# servo-ctrl.net
KiCad netlist of a schematic drawn in EAGLE
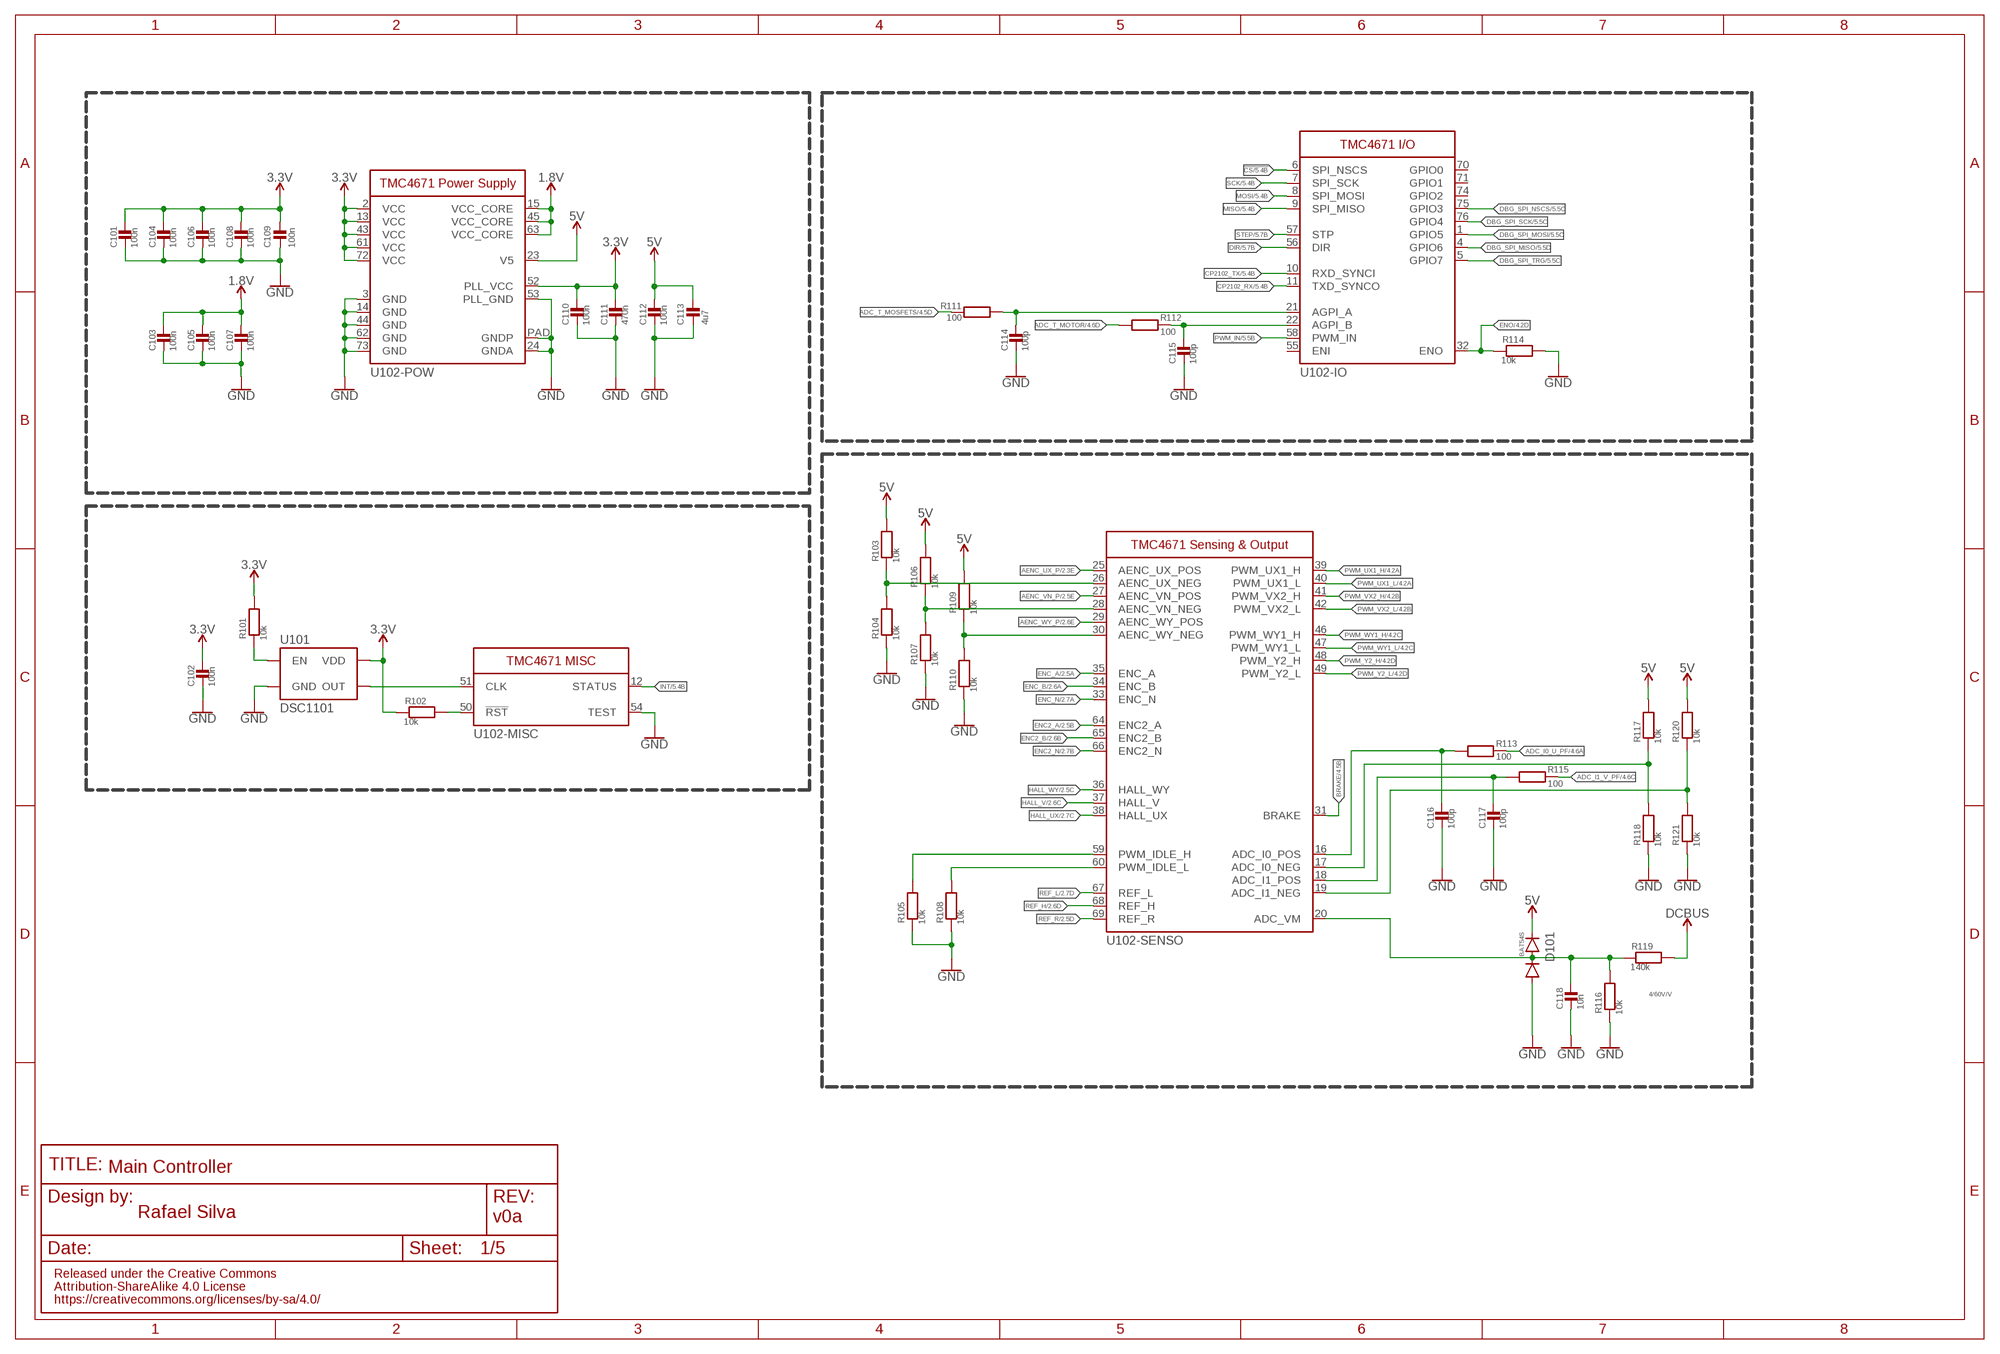
[diagram p0: schematic, sheet 1]
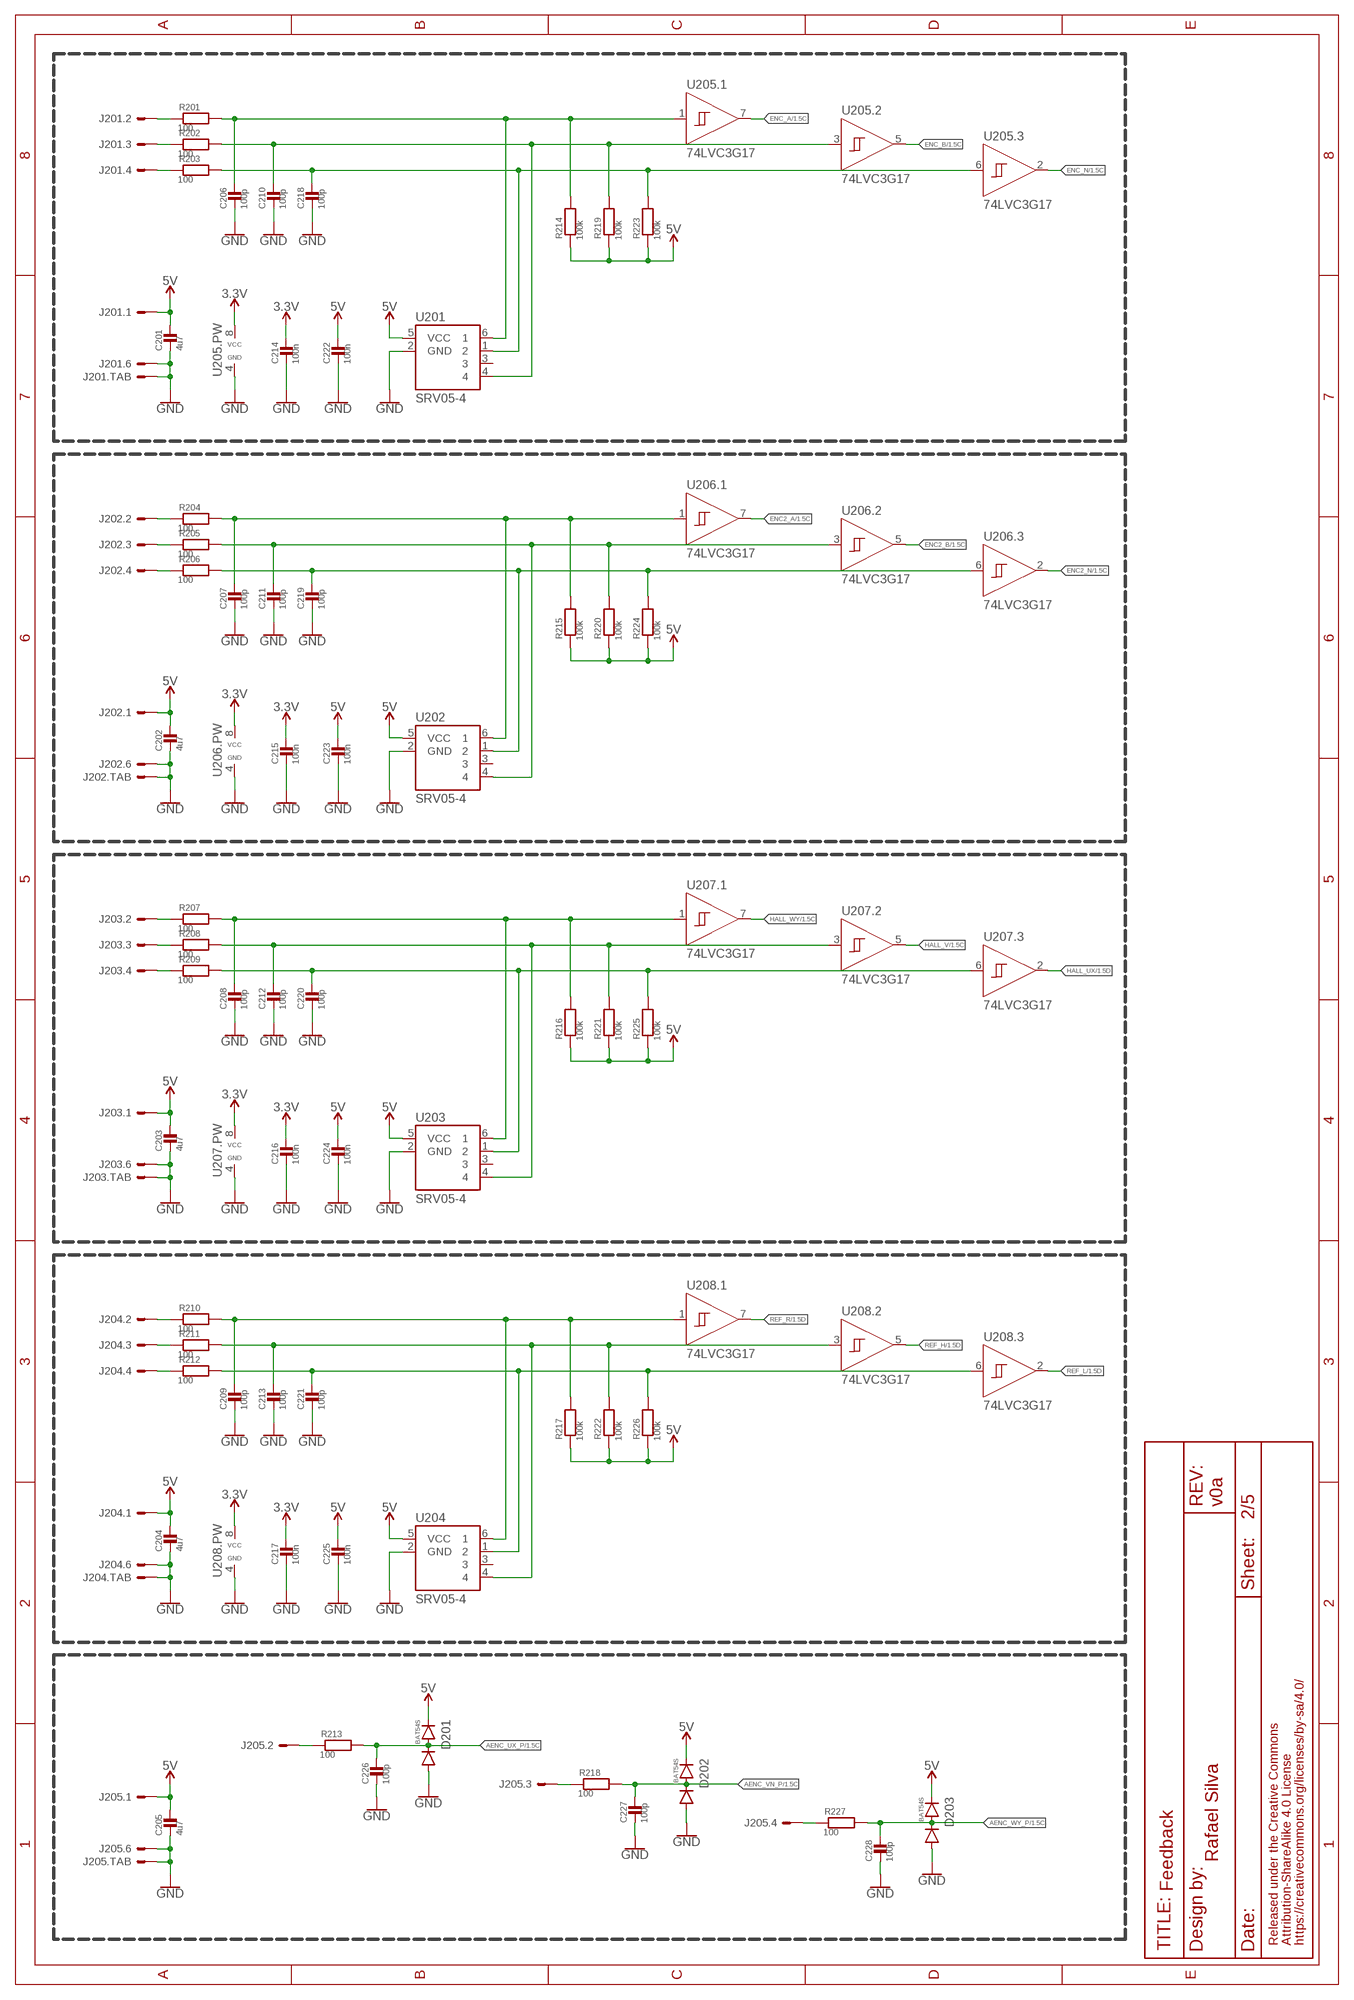
[diagram p1: schematic, sheet 2]
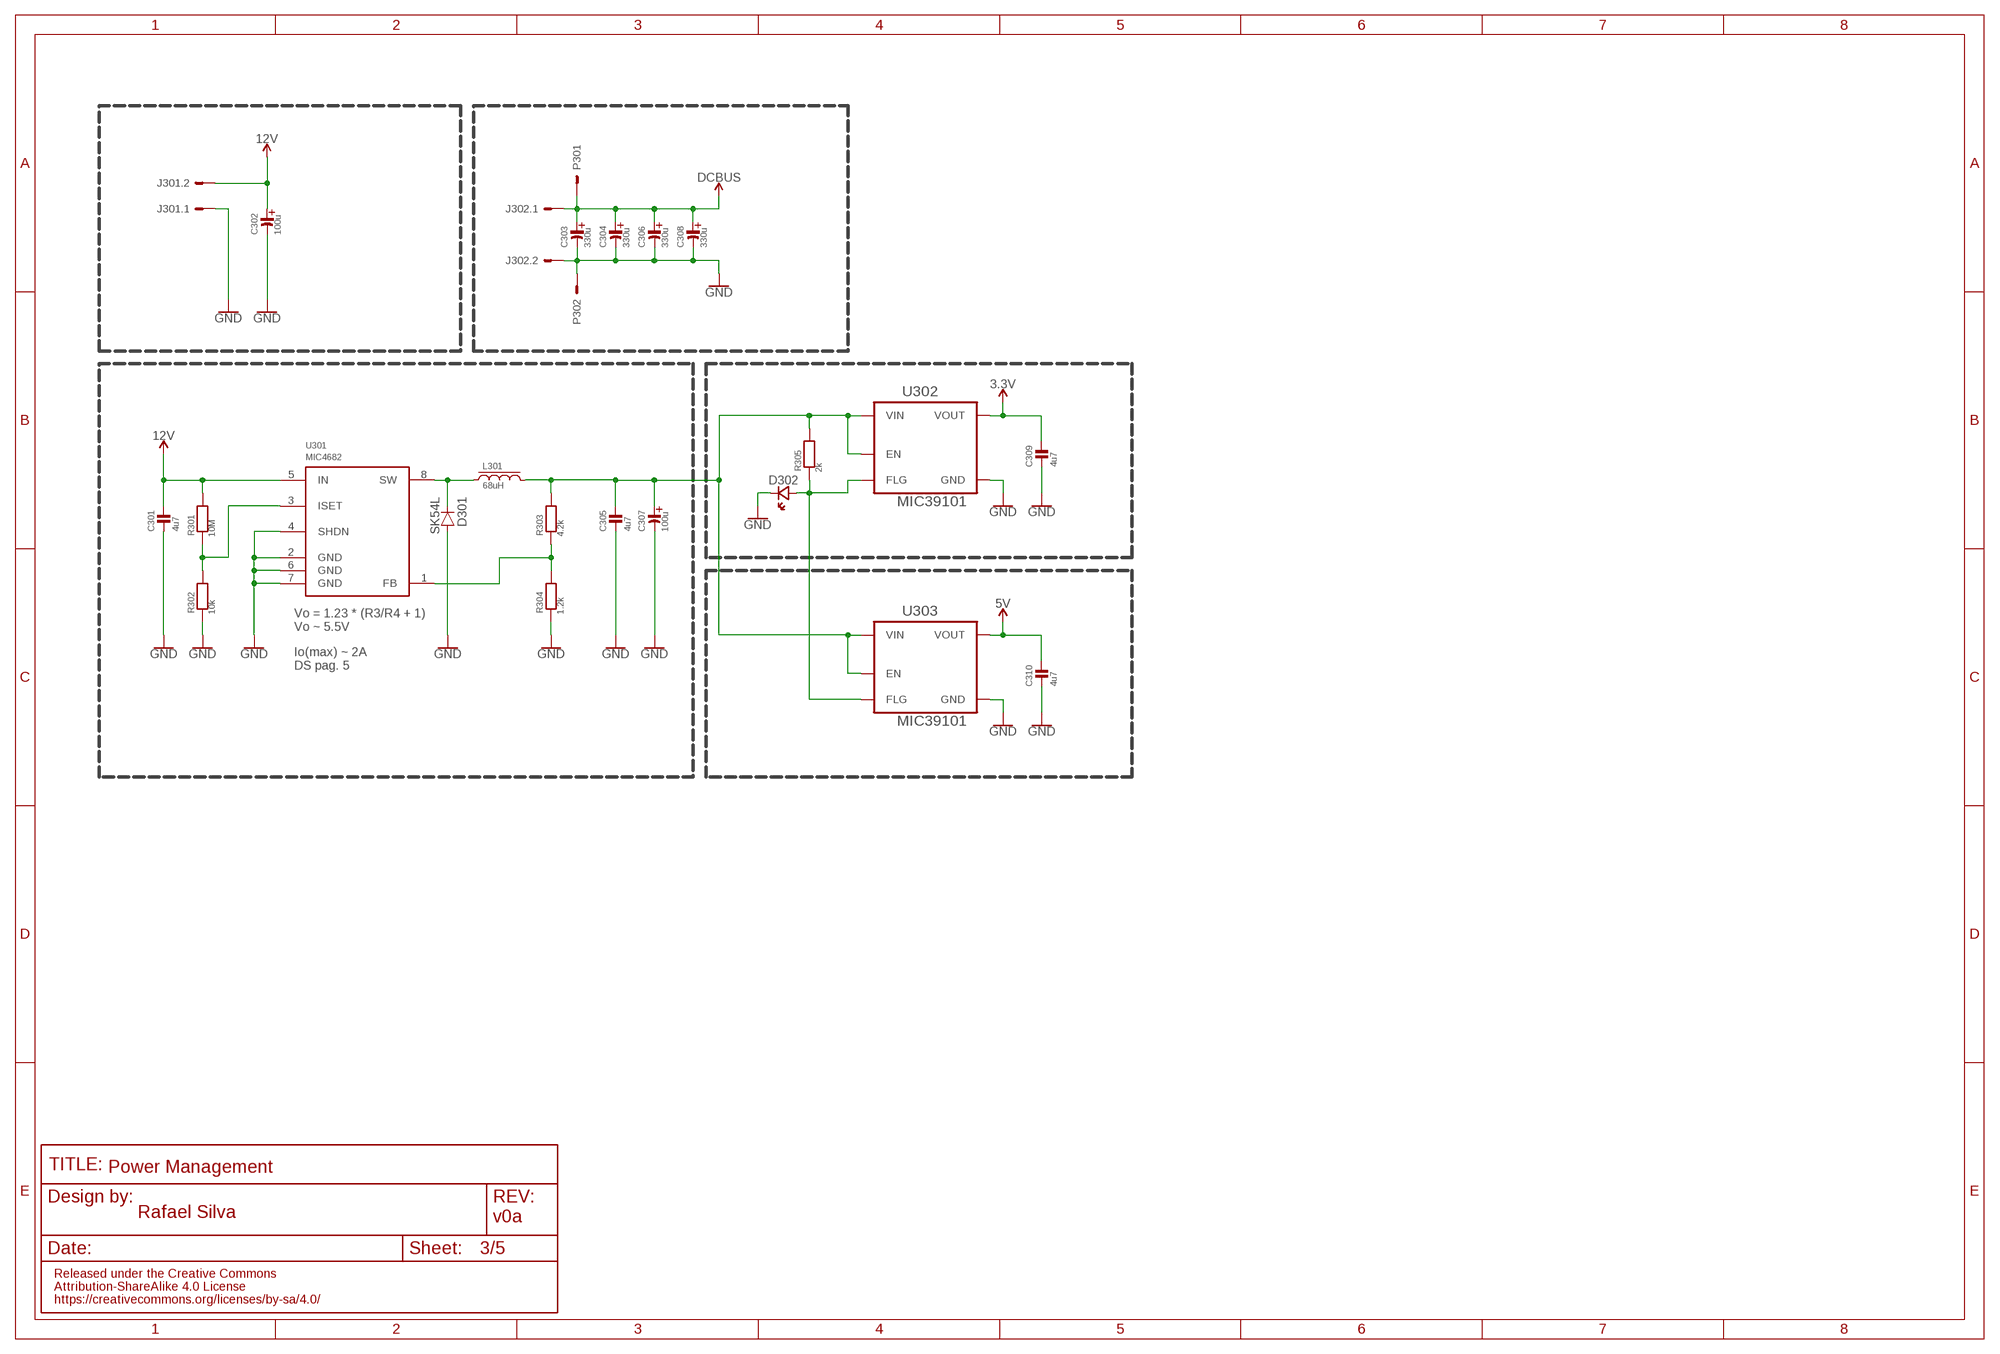
[diagram p2: schematic, sheet 3]
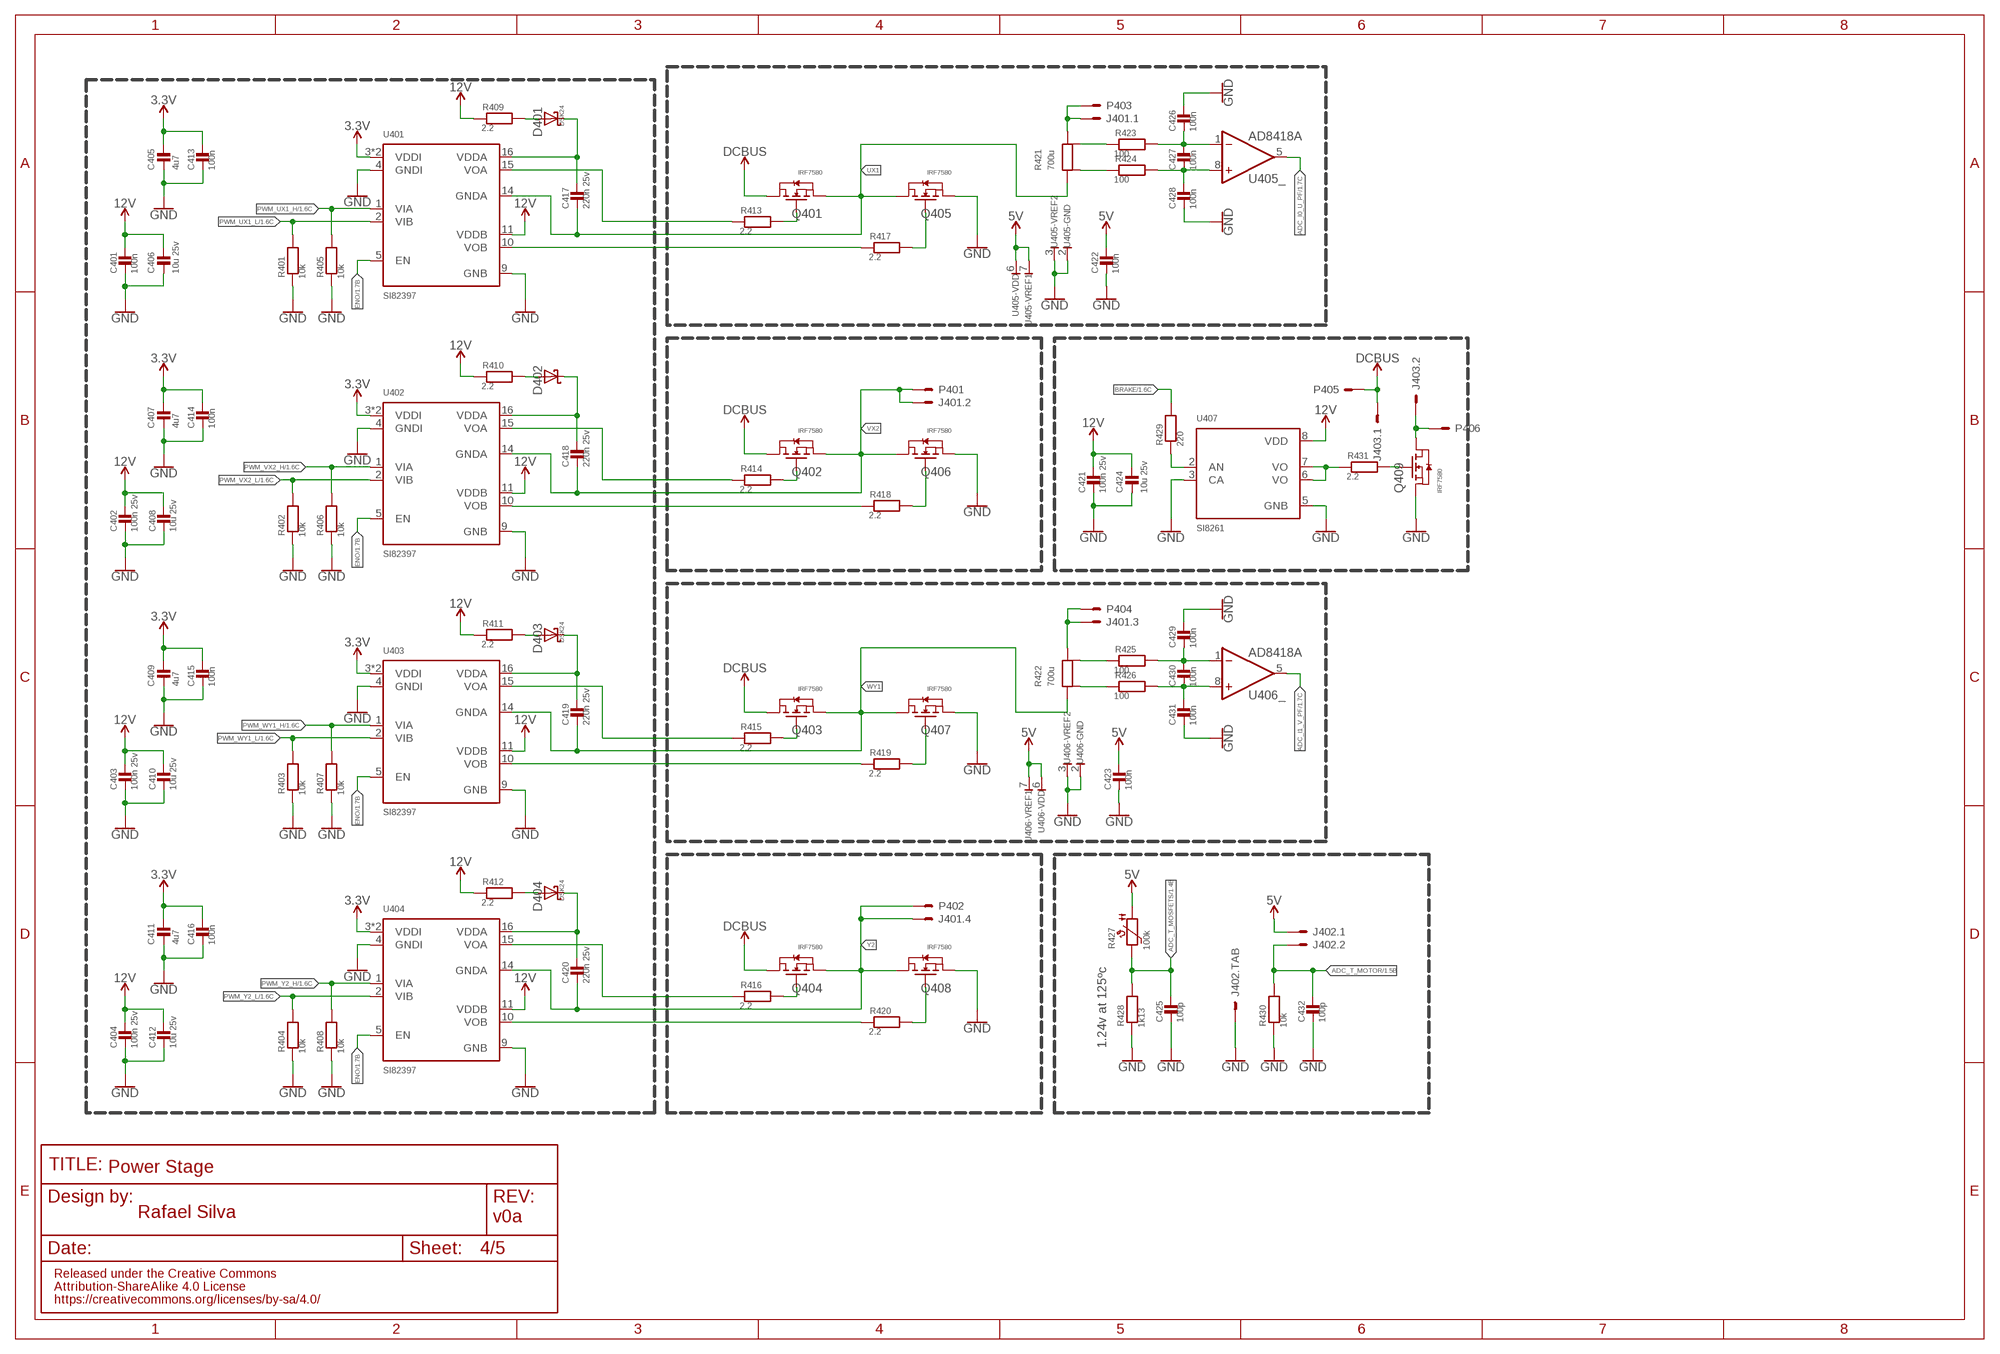
[diagram p3: schematic, sheet 4]
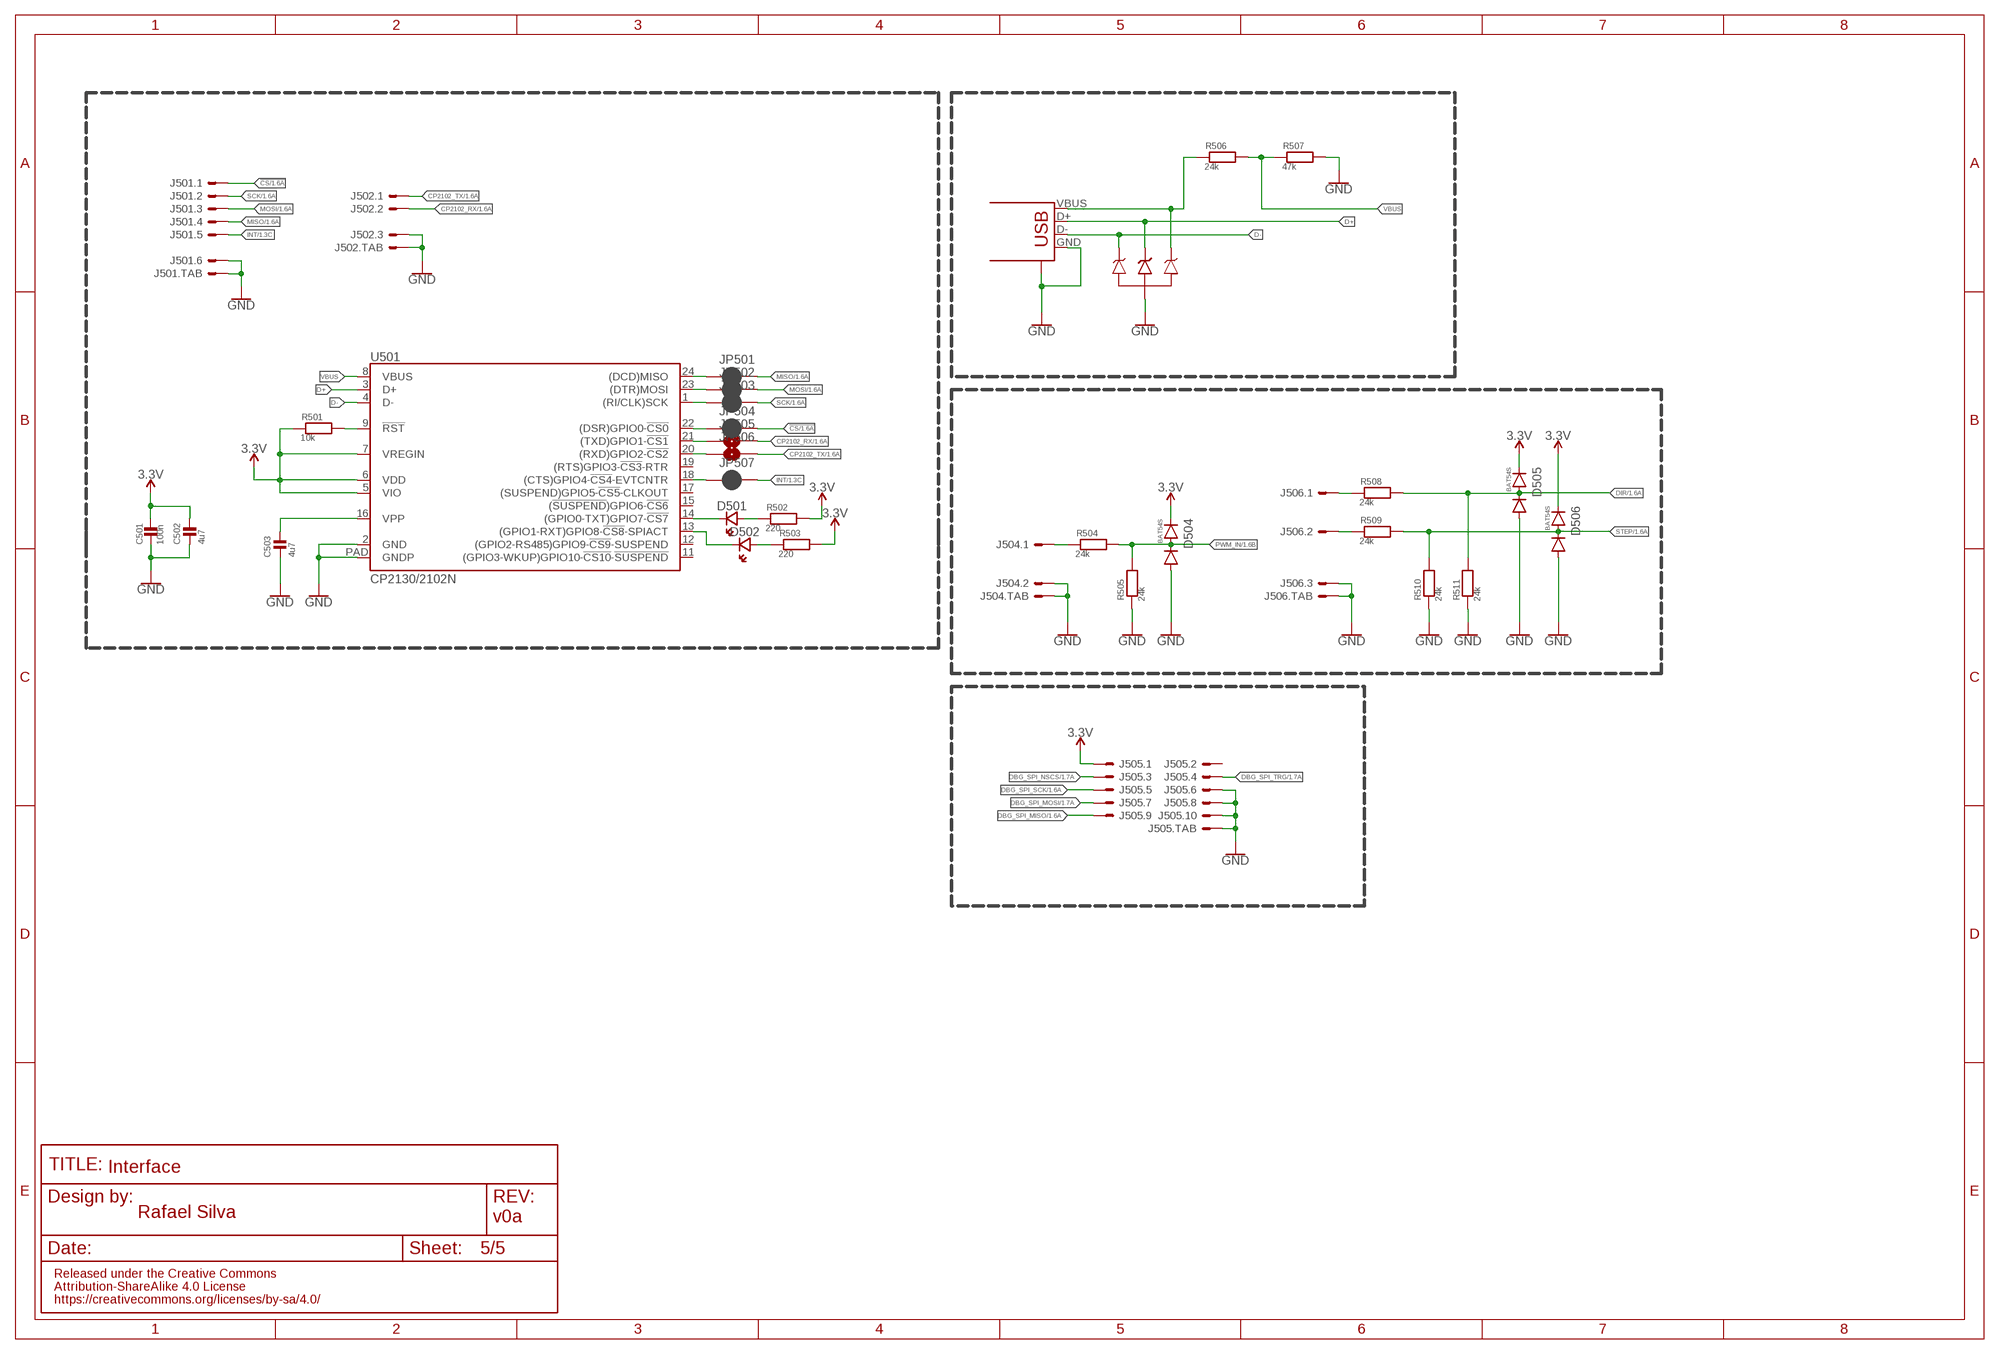
[diagram p4: schematic, sheet 5]

(export (version "E")
  (design (tool "Eeschema 10.0.6"))
  (components
    (comp (ref "C501")
      (value "100n")
      (footprint "eagle-import:0603_WAVE")
      (libsource (lib "eagle-import") (part "MLCC0603"))
    )
    (comp (ref "C502")
      (value "4u7")
      (footprint "eagle-import:0603_WAVE")
      (libsource (lib "eagle-import") (part "MLCC0603"))
    )
    (comp (ref "C503")
      (value "4u7")
      (footprint "eagle-import:0603_WAVE")
      (libsource (lib "eagle-import") (part "MLCC0603"))
    )
    (comp (ref "D501")
      (value "LED0603")
      (footprint "eagle-import:CHIPLED_0603")
      (libsource (lib "eagle-import") (part "LED0603"))
    )
    (comp (ref "D502")
      (value "LED0603")
      (footprint "eagle-import:CHIPLED_0603")
      (libsource (lib "eagle-import") (part "LED0603"))
    )
    (comp (ref "D503")
      (value "SP0503BAHT")
      (footprint "eagle-import:SOT143")
      (libsource (lib "eagle-import") (part "SP0503BAHT"))
    )
    (comp (ref "D504")
      (value "BAT54S")
      (footprint "eagle-import:SOT-23-3")
      (libsource (lib "eagle-import") (part "BAT54S"))
    )
    (comp (ref "D505")
      (value "BAT54S")
      (footprint "eagle-import:SOT-23-3")
      (libsource (lib "eagle-import") (part "BAT54S"))
    )
    (comp (ref "D506")
      (value "BAT54S")
      (footprint "eagle-import:SOT-23-3")
      (libsource (lib "eagle-import") (part "BAT54S"))
    )
    (comp (ref "J501")
      (value "SH-6")
      (footprint "eagle-import:SM06B-SSR-H-TB")
      (libsource (lib "eagle-import") (part "SH-6"))
    )
    (comp (ref "J502")
      (value "SH-3")
      (footprint "eagle-import:SM03B-SSR-H-TB")
      (libsource (lib "eagle-import") (part "SH-3"))
    )
    (comp (ref "J503")
      (value "USB-SHIELD")
      (footprint "eagle-import:USB-M-S1")
      (libsource (lib "eagle-import") (part "USB-SHIELD"))
    )
    (comp (ref "J504")
      (value "SH-2")
      (footprint "eagle-import:SM02B-SSR-H-TB")
      (libsource (lib "eagle-import") (part "SH-2"))
    )
    (comp (ref "J505")
      (value "F20F-10DP-1V")
      (footprint "eagle-import:F20F-10DP-1V")
      (libsource (lib "eagle-import") (part "F20F-10DP-1V"))
    )
    (comp (ref "J506")
      (value "SH-3")
      (footprint "eagle-import:SM03B-SSR-H-TB")
      (libsource (lib "eagle-import") (part "SH-3"))
    )
    (comp (ref "JP501")
      (value "JUMPER-SMT_2_NC_PASTE_SILK")
      (footprint "eagle-import:SMT-JUMPER_2_NC_PASTE_SILK")
      (libsource (lib "eagle-import") (part "JUMPER-SMT_2_NC_PASTE_SILK"))
    )
    (comp (ref "JP502")
      (value "JUMPER-SMT_2_NC_PASTE_SILK")
      (footprint "eagle-import:SMT-JUMPER_2_NC_PASTE_SILK")
      (libsource (lib "eagle-import") (part "JUMPER-SMT_2_NC_PASTE_SILK"))
    )
    (comp (ref "JP503")
      (value "JUMPER-SMT_2_NC_PASTE_SILK")
      (footprint "eagle-import:SMT-JUMPER_2_NC_PASTE_SILK")
      (libsource (lib "eagle-import") (part "JUMPER-SMT_2_NC_PASTE_SILK"))
    )
    (comp (ref "JP504")
      (value "JUMPER-SMT_2_NC_PASTE_SILK")
      (footprint "eagle-import:SMT-JUMPER_2_NC_PASTE_SILK")
      (libsource (lib "eagle-import") (part "JUMPER-SMT_2_NC_PASTE_SILK"))
    )
    (comp (ref "JP505")
      (value "JUMPER-SMT_2_NO_SILK")
      (footprint "eagle-import:SMT-JUMPER_2_NO_SILK")
      (libsource (lib "eagle-import") (part "JUMPER-SMT_2_NO_SILK"))
    )
    (comp (ref "JP506")
      (value "JUMPER-SMT_2_NO_SILK")
      (footprint "eagle-import:SMT-JUMPER_2_NO_SILK")
      (libsource (lib "eagle-import") (part "JUMPER-SMT_2_NO_SILK"))
    )
    (comp (ref "JP507")
      (value "JUMPER-SMT_2_NC_PASTE_SILK")
      (footprint "eagle-import:SMT-JUMPER_2_NC_PASTE_SILK")
      (libsource (lib "eagle-import") (part "JUMPER-SMT_2_NC_PASTE_SILK"))
    )
    (comp (ref "R501")
      (value "10k")
      (footprint "eagle-import:0603_WAVE")
      (libsource (lib "eagle-import") (part "RESISTOR0603"))
    )
    (comp (ref "R502")
      (value "220")
      (footprint "eagle-import:0603_WAVE")
      (libsource (lib "eagle-import") (part "RESISTOR0603"))
    )
    (comp (ref "R503")
      (value "220")
      (footprint "eagle-import:0603_WAVE")
      (libsource (lib "eagle-import") (part "RESISTOR0603"))
    )
    (comp (ref "R504")
      (value "24k")
      (footprint "eagle-import:0603_WAVE")
      (libsource (lib "eagle-import") (part "RESISTOR0603"))
    )
    (comp (ref "R505")
      (value "24k")
      (footprint "eagle-import:0603_WAVE")
      (libsource (lib "eagle-import") (part "RESISTOR0603"))
    )
    (comp (ref "R506")
      (value "24k")
      (footprint "eagle-import:0603_WAVE")
      (libsource (lib "eagle-import") (part "RESISTOR0603"))
    )
    (comp (ref "R507")
      (value "47k")
      (footprint "eagle-import:0603_WAVE")
      (libsource (lib "eagle-import") (part "RESISTOR0603"))
    )
    (comp (ref "R508")
      (value "24k")
      (footprint "eagle-import:0603_WAVE")
      (libsource (lib "eagle-import") (part "RESISTOR0603"))
    )
    (comp (ref "R509")
      (value "24k")
      (footprint "eagle-import:0603_WAVE")
      (libsource (lib "eagle-import") (part "RESISTOR0603"))
    )
    (comp (ref "R510")
      (value "24k")
      (footprint "eagle-import:0603_WAVE")
      (libsource (lib "eagle-import") (part "RESISTOR0603"))
    )
    (comp (ref "R511")
      (value "24k")
      (footprint "eagle-import:0603_WAVE")
      (libsource (lib "eagle-import") (part "RESISTOR0603"))
    )
    (comp (ref "U501")
      (value "CP2130/2102N")
      (footprint "eagle-import:QFN24")
      (libsource (lib "eagle-import") (part "CP2130/2102N"))
    )
    (comp (ref "C101")
      (value "100n")
      (footprint "eagle-import:0603_WAVE")
      (libsource (lib "eagle-import") (part "MLCC0603"))
    )
    (comp (ref "C102")
      (value "100n")
      (footprint "eagle-import:0603_WAVE")
      (libsource (lib "eagle-import") (part "MLCC0603"))
    )
    (comp (ref "C103")
      (value "100n")
      (footprint "eagle-import:0603_WAVE")
      (libsource (lib "eagle-import") (part "MLCC0603"))
    )
    (comp (ref "C104")
      (value "100n")
      (footprint "eagle-import:0603_WAVE")
      (libsource (lib "eagle-import") (part "MLCC0603"))
    )
    (comp (ref "C105")
      (value "100n")
      (footprint "eagle-import:0603_WAVE")
      (libsource (lib "eagle-import") (part "MLCC0603"))
    )
    (comp (ref "C106")
      (value "100n")
      (footprint "eagle-import:0603_WAVE")
      (libsource (lib "eagle-import") (part "MLCC0603"))
    )
    (comp (ref "C107")
      (value "100n")
      (footprint "eagle-import:0603_WAVE")
      (libsource (lib "eagle-import") (part "MLCC0603"))
    )
    (comp (ref "C108")
      (value "100n")
      (footprint "eagle-import:0603_WAVE")
      (libsource (lib "eagle-import") (part "MLCC0603"))
    )
    (comp (ref "C109")
      (value "100n")
      (footprint "eagle-import:0603_WAVE")
      (libsource (lib "eagle-import") (part "MLCC0603"))
    )
    (comp (ref "C110")
      (value "100n")
      (footprint "eagle-import:0603_WAVE")
      (libsource (lib "eagle-import") (part "MLCC0603"))
    )
    (comp (ref "C111")
      (value "470n")
      (footprint "eagle-import:0603_WAVE")
      (libsource (lib "eagle-import") (part "MLCC0603"))
    )
    (comp (ref "C112")
      (value "100n")
      (footprint "eagle-import:0603_WAVE")
      (libsource (lib "eagle-import") (part "MLCC0603"))
    )
    (comp (ref "C113")
      (value "4u7")
      (footprint "eagle-import:0603_WAVE")
      (libsource (lib "eagle-import") (part "MLCC0603"))
    )
    (comp (ref "C114")
      (value "100p")
      (footprint "eagle-import:0603_WAVE")
      (libsource (lib "eagle-import") (part "MLCC0603"))
    )
    (comp (ref "C115")
      (value "100p")
      (footprint "eagle-import:0603_WAVE")
      (libsource (lib "eagle-import") (part "MLCC0603"))
    )
    (comp (ref "C116")
      (value "100p")
      (footprint "eagle-import:0603_WAVE")
      (libsource (lib "eagle-import") (part "MLCC0603"))
    )
    (comp (ref "C117")
      (value "100p")
      (footprint "eagle-import:0603_WAVE")
      (libsource (lib "eagle-import") (part "MLCC0603"))
    )
    (comp (ref "C118")
      (value "10n")
      (footprint "eagle-import:0603_WAVE")
      (libsource (lib "eagle-import") (part "MLCC0603"))
    )
    (comp (ref "D101")
      (value "BAT54S")
      (footprint "eagle-import:SOT-23-3")
      (libsource (lib "eagle-import") (part "BAT54S"))
    )
    (comp (ref "R101")
      (value "10k")
      (footprint "eagle-import:0603_WAVE")
      (libsource (lib "eagle-import") (part "RESISTOR0603"))
    )
    (comp (ref "R102")
      (value "10k")
      (footprint "eagle-import:0603_WAVE")
      (libsource (lib "eagle-import") (part "RESISTOR0603"))
    )
    (comp (ref "R103")
      (value "10k")
      (footprint "eagle-import:0603_WAVE")
      (libsource (lib "eagle-import") (part "RESISTOR0603"))
    )
    (comp (ref "R104")
      (value "10k")
      (footprint "eagle-import:0603_WAVE")
      (libsource (lib "eagle-import") (part "RESISTOR0603"))
    )
    (comp (ref "R105")
      (value "10k")
      (footprint "eagle-import:0603_WAVE")
      (libsource (lib "eagle-import") (part "RESISTOR0603"))
    )
    (comp (ref "R106")
      (value "10k")
      (footprint "eagle-import:0603_WAVE")
      (libsource (lib "eagle-import") (part "RESISTOR0603"))
    )
    (comp (ref "R107")
      (value "10k")
      (footprint "eagle-import:0603_WAVE")
      (libsource (lib "eagle-import") (part "RESISTOR0603"))
    )
    (comp (ref "R108")
      (value "10k")
      (footprint "eagle-import:0603_WAVE")
      (libsource (lib "eagle-import") (part "RESISTOR0603"))
    )
    (comp (ref "R109")
      (value "10k")
      (footprint "eagle-import:0603_WAVE")
      (libsource (lib "eagle-import") (part "RESISTOR0603"))
    )
    (comp (ref "R110")
      (value "10k")
      (footprint "eagle-import:0603_WAVE")
      (libsource (lib "eagle-import") (part "RESISTOR0603"))
    )
    (comp (ref "R111")
      (value "100")
      (footprint "eagle-import:0603_WAVE")
      (libsource (lib "eagle-import") (part "RESISTOR0603"))
    )
    (comp (ref "R112")
      (value "100")
      (footprint "eagle-import:0603_WAVE")
      (libsource (lib "eagle-import") (part "RESISTOR0603"))
    )
    (comp (ref "R113")
      (value "100")
      (footprint "eagle-import:0603_WAVE")
      (libsource (lib "eagle-import") (part "RESISTOR0603"))
    )
    (comp (ref "R114")
      (value "10k")
      (footprint "eagle-import:0603_WAVE")
      (libsource (lib "eagle-import") (part "RESISTOR0603"))
    )
    (comp (ref "R115")
      (value "100")
      (footprint "eagle-import:0603_WAVE")
      (libsource (lib "eagle-import") (part "RESISTOR0603"))
    )
    (comp (ref "R116")
      (value "10k")
      (footprint "eagle-import:0603_WAVE")
      (libsource (lib "eagle-import") (part "RESISTOR0603"))
    )
    (comp (ref "R117")
      (value "10k")
      (footprint "eagle-import:0603_WAVE")
      (libsource (lib "eagle-import") (part "RESISTOR0603"))
    )
    (comp (ref "R118")
      (value "10k")
      (footprint "eagle-import:0603_WAVE")
      (libsource (lib "eagle-import") (part "RESISTOR0603"))
    )
    (comp (ref "R119")
      (value "140k")
      (footprint "eagle-import:0603_WAVE")
      (libsource (lib "eagle-import") (part "RESISTOR0603"))
    )
    (comp (ref "R120")
      (value "10k")
      (footprint "eagle-import:0603_WAVE")
      (libsource (lib "eagle-import") (part "RESISTOR0603"))
    )
    (comp (ref "R121")
      (value "10k")
      (footprint "eagle-import:0603_WAVE")
      (libsource (lib "eagle-import") (part "RESISTOR0603"))
    )
    (comp (ref "U101")
      (value "DSC1101")
      (footprint "eagle-import:CDFN_5X3.2")
      (libsource (lib "eagle-import") (part "DSC1101"))
    )
    (comp (ref "U102")
      (value "TMC4671")
      (footprint "eagle-import:QFN76")
      (libsource (lib "eagle-import") (part "TMC4671"))
    )
    (comp (ref "C201")
      (value "4u7")
      (footprint "eagle-import:0603_WAVE")
      (libsource (lib "eagle-import") (part "MLCC0603"))
    )
    (comp (ref "C202")
      (value "4u7")
      (footprint "eagle-import:0603_WAVE")
      (libsource (lib "eagle-import") (part "MLCC0603"))
    )
    (comp (ref "C203")
      (value "4u7")
      (footprint "eagle-import:0603_WAVE")
      (libsource (lib "eagle-import") (part "MLCC0603"))
    )
    (comp (ref "C204")
      (value "4u7")
      (footprint "eagle-import:0603_WAVE")
      (libsource (lib "eagle-import") (part "MLCC0603"))
    )
    (comp (ref "C205")
      (value "4u7")
      (footprint "eagle-import:0603_WAVE")
      (libsource (lib "eagle-import") (part "MLCC0603"))
    )
    (comp (ref "C206")
      (value "100p")
      (footprint "eagle-import:0603_WAVE")
      (libsource (lib "eagle-import") (part "MLCC0603"))
    )
    (comp (ref "C207")
      (value "100p")
      (footprint "eagle-import:0603_WAVE")
      (libsource (lib "eagle-import") (part "MLCC0603"))
    )
    (comp (ref "C208")
      (value "100p")
      (footprint "eagle-import:0603_WAVE")
      (libsource (lib "eagle-import") (part "MLCC0603"))
    )
    (comp (ref "C209")
      (value "100p")
      (footprint "eagle-import:0603_WAVE")
      (libsource (lib "eagle-import") (part "MLCC0603"))
    )
    (comp (ref "C210")
      (value "100p")
      (footprint "eagle-import:0603_WAVE")
      (libsource (lib "eagle-import") (part "MLCC0603"))
    )
    (comp (ref "C211")
      (value "100p")
      (footprint "eagle-import:0603_WAVE")
      (libsource (lib "eagle-import") (part "MLCC0603"))
    )
    (comp (ref "C212")
      (value "100p")
      (footprint "eagle-import:0603_WAVE")
      (libsource (lib "eagle-import") (part "MLCC0603"))
    )
    (comp (ref "C213")
      (value "100p")
      (footprint "eagle-import:0603_WAVE")
      (libsource (lib "eagle-import") (part "MLCC0603"))
    )
    (comp (ref "C214")
      (value "100n")
      (footprint "eagle-import:0603_WAVE")
      (libsource (lib "eagle-import") (part "MLCC0603"))
    )
    (comp (ref "C215")
      (value "100n")
      (footprint "eagle-import:0603_WAVE")
      (libsource (lib "eagle-import") (part "MLCC0603"))
    )
    (comp (ref "C216")
      (value "100n")
      (footprint "eagle-import:0603_WAVE")
      (libsource (lib "eagle-import") (part "MLCC0603"))
    )
    (comp (ref "C217")
      (value "100n")
      (footprint "eagle-import:0603_WAVE")
      (libsource (lib "eagle-import") (part "MLCC0603"))
    )
    (comp (ref "C218")
      (value "100p")
      (footprint "eagle-import:0603_WAVE")
      (libsource (lib "eagle-import") (part "MLCC0603"))
    )
    (comp (ref "C219")
      (value "100p")
      (footprint "eagle-import:0603_WAVE")
      (libsource (lib "eagle-import") (part "MLCC0603"))
    )
    (comp (ref "C220")
      (value "100p")
      (footprint "eagle-import:0603_WAVE")
      (libsource (lib "eagle-import") (part "MLCC0603"))
    )
    (comp (ref "C221")
      (value "100p")
      (footprint "eagle-import:0603_WAVE")
      (libsource (lib "eagle-import") (part "MLCC0603"))
    )
    (comp (ref "C222")
      (value "100n")
      (footprint "eagle-import:0603_WAVE")
      (libsource (lib "eagle-import") (part "MLCC0603"))
    )
    (comp (ref "C223")
      (value "100n")
      (footprint "eagle-import:0603_WAVE")
      (libsource (lib "eagle-import") (part "MLCC0603"))
    )
    (comp (ref "C224")
      (value "100n")
      (footprint "eagle-import:0603_WAVE")
      (libsource (lib "eagle-import") (part "MLCC0603"))
    )
    (comp (ref "C225")
      (value "100n")
      (footprint "eagle-import:0603_WAVE")
      (libsource (lib "eagle-import") (part "MLCC0603"))
    )
    (comp (ref "C226")
      (value "100p")
      (footprint "eagle-import:0603_WAVE")
      (libsource (lib "eagle-import") (part "MLCC0603"))
    )
    (comp (ref "C227")
      (value "100p")
      (footprint "eagle-import:0603_WAVE")
      (libsource (lib "eagle-import") (part "MLCC0603"))
    )
    (comp (ref "C228")
      (value "100p")
      (footprint "eagle-import:0603_WAVE")
      (libsource (lib "eagle-import") (part "MLCC0603"))
    )
    (comp (ref "D201")
      (value "BAT54S")
      (footprint "eagle-import:SOT-23-3")
      (libsource (lib "eagle-import") (part "BAT54S"))
    )
    (comp (ref "D202")
      (value "BAT54S")
      (footprint "eagle-import:SOT-23-3")
      (libsource (lib "eagle-import") (part "BAT54S"))
    )
    (comp (ref "D203")
      (value "BAT54S")
      (footprint "eagle-import:SOT-23-3")
      (libsource (lib "eagle-import") (part "BAT54S"))
    )
    (comp (ref "J201")
      (value "SH-5")
      (footprint "eagle-import:SM05B-SSR-H-TB")
      (libsource (lib "eagle-import") (part "SH-5"))
    )
    (comp (ref "J202")
      (value "SH-5")
      (footprint "eagle-import:SM05B-SSR-H-TB")
      (libsource (lib "eagle-import") (part "SH-5"))
    )
    (comp (ref "J203")
      (value "SH-5")
      (footprint "eagle-import:SM05B-SSR-H-TB")
      (libsource (lib "eagle-import") (part "SH-5"))
    )
    (comp (ref "J204")
      (value "SH-5")
      (footprint "eagle-import:SM05B-SSR-H-TB")
      (libsource (lib "eagle-import") (part "SH-5"))
    )
    (comp (ref "J205")
      (value "SH-5")
      (footprint "eagle-import:SM05B-SSR-H-TB")
      (libsource (lib "eagle-import") (part "SH-5"))
    )
    (comp (ref "R201")
      (value "100")
      (footprint "eagle-import:0603_WAVE")
      (libsource (lib "eagle-import") (part "RESISTOR0603"))
    )
    (comp (ref "R202")
      (value "100")
      (footprint "eagle-import:0603_WAVE")
      (libsource (lib "eagle-import") (part "RESISTOR0603"))
    )
    (comp (ref "R203")
      (value "100")
      (footprint "eagle-import:0603_WAVE")
      (libsource (lib "eagle-import") (part "RESISTOR0603"))
    )
    (comp (ref "R204")
      (value "100")
      (footprint "eagle-import:0603_WAVE")
      (libsource (lib "eagle-import") (part "RESISTOR0603"))
    )
    (comp (ref "R205")
      (value "100")
      (footprint "eagle-import:0603_WAVE")
      (libsource (lib "eagle-import") (part "RESISTOR0603"))
    )
    (comp (ref "R206")
      (value "100")
      (footprint "eagle-import:0603_WAVE")
      (libsource (lib "eagle-import") (part "RESISTOR0603"))
    )
    (comp (ref "R207")
      (value "100")
      (footprint "eagle-import:0603_WAVE")
      (libsource (lib "eagle-import") (part "RESISTOR0603"))
    )
    (comp (ref "R208")
      (value "100")
      (footprint "eagle-import:0603_WAVE")
      (libsource (lib "eagle-import") (part "RESISTOR0603"))
    )
    (comp (ref "R209")
      (value "100")
      (footprint "eagle-import:0603_WAVE")
      (libsource (lib "eagle-import") (part "RESISTOR0603"))
    )
    (comp (ref "R210")
      (value "100")
      (footprint "eagle-import:0603_WAVE")
      (libsource (lib "eagle-import") (part "RESISTOR0603"))
    )
    (comp (ref "R211")
      (value "100")
      (footprint "eagle-import:0603_WAVE")
      (libsource (lib "eagle-import") (part "RESISTOR0603"))
    )
    (comp (ref "R212")
      (value "100")
      (footprint "eagle-import:0603_WAVE")
      (libsource (lib "eagle-import") (part "RESISTOR0603"))
    )
    (comp (ref "R213")
      (value "100")
      (footprint "eagle-import:0603_WAVE")
      (libsource (lib "eagle-import") (part "RESISTOR0603"))
    )
    (comp (ref "R214")
      (value "100k")
      (footprint "eagle-import:0603_WAVE")
      (libsource (lib "eagle-import") (part "RESISTOR0603"))
    )
    (comp (ref "R215")
      (value "100k")
      (footprint "eagle-import:0603_WAVE")
      (libsource (lib "eagle-import") (part "RESISTOR0603"))
    )
    (comp (ref "R216")
      (value "100k")
      (footprint "eagle-import:0603_WAVE")
      (libsource (lib "eagle-import") (part "RESISTOR0603"))
    )
    (comp (ref "R217")
      (value "100k")
      (footprint "eagle-import:0603_WAVE")
      (libsource (lib "eagle-import") (part "RESISTOR0603"))
    )
    (comp (ref "R218")
      (value "100")
      (footprint "eagle-import:0603_WAVE")
      (libsource (lib "eagle-import") (part "RESISTOR0603"))
    )
    (comp (ref "R219")
      (value "100k")
      (footprint "eagle-import:0603_WAVE")
      (libsource (lib "eagle-import") (part "RESISTOR0603"))
    )
    (comp (ref "R220")
      (value "100k")
      (footprint "eagle-import:0603_WAVE")
      (libsource (lib "eagle-import") (part "RESISTOR0603"))
    )
    (comp (ref "R221")
      (value "100k")
      (footprint "eagle-import:0603_WAVE")
      (libsource (lib "eagle-import") (part "RESISTOR0603"))
    )
    (comp (ref "R222")
      (value "100k")
      (footprint "eagle-import:0603_WAVE")
      (libsource (lib "eagle-import") (part "RESISTOR0603"))
    )
    (comp (ref "R223")
      (value "100k")
      (footprint "eagle-import:0603_WAVE")
      (libsource (lib "eagle-import") (part "RESISTOR0603"))
    )
    (comp (ref "R224")
      (value "100k")
      (footprint "eagle-import:0603_WAVE")
      (libsource (lib "eagle-import") (part "RESISTOR0603"))
    )
    (comp (ref "R225")
      (value "100k")
      (footprint "eagle-import:0603_WAVE")
      (libsource (lib "eagle-import") (part "RESISTOR0603"))
    )
    (comp (ref "R226")
      (value "100k")
      (footprint "eagle-import:0603_WAVE")
      (libsource (lib "eagle-import") (part "RESISTOR0603"))
    )
    (comp (ref "R227")
      (value "100")
      (footprint "eagle-import:0603_WAVE")
      (libsource (lib "eagle-import") (part "RESISTOR0603"))
    )
    (comp (ref "U201")
      (value "SRV05-4")
      (footprint "eagle-import:SOT23-6")
      (libsource (lib "eagle-import") (part "SRV05-4"))
    )
    (comp (ref "U202")
      (value "SRV05-4")
      (footprint "eagle-import:SOT23-6")
      (libsource (lib "eagle-import") (part "SRV05-4"))
    )
    (comp (ref "U203")
      (value "SRV05-4")
      (footprint "eagle-import:SOT23-6")
      (libsource (lib "eagle-import") (part "SRV05-4"))
    )
    (comp (ref "U204")
      (value "SRV05-4")
      (footprint "eagle-import:SOT23-6")
      (libsource (lib "eagle-import") (part "SRV05-4"))
    )
    (comp (ref "U205")
      (value "74LVC3G17")
      (footprint "eagle-import:TSSOP-8")
      (libsource (lib "eagle-import") (part "74LVC3G17"))
    )
    (comp (ref "U206")
      (value "74LVC3G17")
      (footprint "eagle-import:TSSOP-8")
      (libsource (lib "eagle-import") (part "74LVC3G17"))
    )
    (comp (ref "U207")
      (value "74LVC3G17")
      (footprint "eagle-import:TSSOP-8")
      (libsource (lib "eagle-import") (part "74LVC3G17"))
    )
    (comp (ref "U208")
      (value "74LVC3G17")
      (footprint "eagle-import:TSSOP-8")
      (libsource (lib "eagle-import") (part "74LVC3G17"))
    )
    (comp (ref "C301")
      (value "4u7")
      (footprint "eagle-import:0603_WAVE")
      (libsource (lib "eagle-import") (part "MLCC0603"))
    )
    (comp (ref "C302")
      (value "100u")
      (footprint "eagle-import:PANASONIC_D")
      (libsource (lib "eagle-import") (part "CAPACITOR_ELD"))
    )
    (comp (ref "C303")
      (value "330u")
      (footprint "eagle-import:PANASONIC_G")
      (libsource (lib "eagle-import") (part "CAPACITOR_ELG"))
    )
    (comp (ref "C304")
      (value "330u")
      (footprint "eagle-import:PANASONIC_G")
      (libsource (lib "eagle-import") (part "CAPACITOR_ELG"))
    )
    (comp (ref "C305")
      (value "4u7")
      (footprint "eagle-import:0603_WAVE")
      (libsource (lib "eagle-import") (part "MLCC0603"))
    )
    (comp (ref "C306")
      (value "330u")
      (footprint "eagle-import:PANASONIC_G")
      (libsource (lib "eagle-import") (part "CAPACITOR_ELG"))
    )
    (comp (ref "C307")
      (value "100u")
      (footprint "eagle-import:PANASONIC_D")
      (libsource (lib "eagle-import") (part "CAPACITOR_ELD"))
    )
    (comp (ref "C308")
      (value "330u")
      (footprint "eagle-import:PANASONIC_G")
      (libsource (lib "eagle-import") (part "CAPACITOR_ELG"))
    )
    (comp (ref "C309")
      (value "4u7")
      (footprint "eagle-import:0603_WAVE")
      (libsource (lib "eagle-import") (part "MLCC0603"))
    )
    (comp (ref "C310")
      (value "4u7")
      (footprint "eagle-import:0603_WAVE")
      (libsource (lib "eagle-import") (part "MLCC0603"))
    )
    (comp (ref "D301")
      (value "SK54L")
      (footprint "eagle-import:DO214AA")
      (libsource (lib "eagle-import") (part "SK54L"))
    )
    (comp (ref "D302")
      (value "LED0603")
      (footprint "eagle-import:CHIPLED_0603")
      (libsource (lib "eagle-import") (part "LED0603"))
    )
    (comp (ref "J301")
      (value "2P-6.35P")
      (footprint "eagle-import:2P-6.35P")
      (libsource (lib "eagle-import") (part "2P-6.35P"))
    )
    (comp (ref "J302")
      (value "2P-6.35P")
      (footprint "eagle-import:2P-6.35P")
      (libsource (lib "eagle-import") (part "2P-6.35P"))
    )
    (comp (ref "L301")
      (value "68uH")
      (footprint "eagle-import:CDRH104R")
      (libsource (lib "eagle-import") (part "INDUCTORCDRH104R"))
    )
    (comp (ref "P301")
      (value "POWPAD")
      (footprint "eagle-import:TH-HP")
      (libsource (lib "eagle-import") (part "POWPAD"))
    )
    (comp (ref "P302")
      (value "POWPAD")
      (footprint "eagle-import:TH-HP")
      (libsource (lib "eagle-import") (part "POWPAD"))
    )
    (comp (ref "R301")
      (value "10M")
      (footprint "eagle-import:0603_WAVE")
      (libsource (lib "eagle-import") (part "RESISTOR0603"))
    )
    (comp (ref "R302")
      (value "10k")
      (footprint "eagle-import:0603_WAVE")
      (libsource (lib "eagle-import") (part "RESISTOR0603"))
    )
    (comp (ref "R303")
      (value "4.2k")
      (footprint "eagle-import:0603_WAVE")
      (libsource (lib "eagle-import") (part "RESISTOR0603"))
    )
    (comp (ref "R304")
      (value "1.2k")
      (footprint "eagle-import:0603_WAVE")
      (libsource (lib "eagle-import") (part "RESISTOR0603"))
    )
    (comp (ref "R305")
      (value "2k")
      (footprint "eagle-import:0603_WAVE")
      (libsource (lib "eagle-import") (part "RESISTOR0603"))
    )
    (comp (ref "U301")
      (value "MIC4682")
      (footprint "eagle-import:SOIC8")
      (libsource (lib "eagle-import") (part "MIC4682"))
    )
    (comp (ref "U302")
      (value "MIC39101")
      (footprint "eagle-import:SOIC8")
      (libsource (lib "eagle-import") (part "MIC39101"))
    )
    (comp (ref "U303")
      (value "MIC39101")
      (footprint "eagle-import:SOIC8")
      (libsource (lib "eagle-import") (part "MIC39101"))
    )
    (comp (ref "C401")
      (value "100n")
      (footprint "eagle-import:0603_WAVE")
      (libsource (lib "eagle-import") (part "MLCC0603"))
    )
    (comp (ref "C402")
      (value "100n 25v")
      (footprint "eagle-import:0603_WAVE")
      (libsource (lib "eagle-import") (part "MLCC0603"))
    )
    (comp (ref "C403")
      (value "100n 25v")
      (footprint "eagle-import:0603_WAVE")
      (libsource (lib "eagle-import") (part "MLCC0603"))
    )
    (comp (ref "C404")
      (value "100n 25v")
      (footprint "eagle-import:0603_WAVE")
      (libsource (lib "eagle-import") (part "MLCC0603"))
    )
    (comp (ref "C405")
      (value "4u7")
      (footprint "eagle-import:0603_WAVE")
      (libsource (lib "eagle-import") (part "MLCC0603"))
    )
    (comp (ref "C406")
      (value "10u 25v")
      (footprint "eagle-import:0603_WAVE")
      (libsource (lib "eagle-import") (part "MLCC0603"))
    )
    (comp (ref "C407")
      (value "4u7")
      (footprint "eagle-import:0603_WAVE")
      (libsource (lib "eagle-import") (part "MLCC0603"))
    )
    (comp (ref "C408")
      (value "10u 25v")
      (footprint "eagle-import:0603_WAVE")
      (libsource (lib "eagle-import") (part "MLCC0603"))
    )
    (comp (ref "C409")
      (value "4u7")
      (footprint "eagle-import:0603_WAVE")
      (libsource (lib "eagle-import") (part "MLCC0603"))
    )
    (comp (ref "C410")
      (value "10u 25v")
      (footprint "eagle-import:0603_WAVE")
      (libsource (lib "eagle-import") (part "MLCC0603"))
    )
    (comp (ref "C411")
      (value "4u7")
      (footprint "eagle-import:0603_WAVE")
      (libsource (lib "eagle-import") (part "MLCC0603"))
    )
    (comp (ref "C412")
      (value "10u 25v")
      (footprint "eagle-import:0603_WAVE")
      (libsource (lib "eagle-import") (part "MLCC0603"))
    )
    (comp (ref "C413")
      (value "100n")
      (footprint "eagle-import:0603_WAVE")
      (libsource (lib "eagle-import") (part "MLCC0603"))
    )
    (comp (ref "C414")
      (value "100n")
      (footprint "eagle-import:0603_WAVE")
      (libsource (lib "eagle-import") (part "MLCC0603"))
    )
    (comp (ref "C415")
      (value "100n")
      (footprint "eagle-import:0603_WAVE")
      (libsource (lib "eagle-import") (part "MLCC0603"))
    )
    (comp (ref "C416")
      (value "100n")
      (footprint "eagle-import:0603_WAVE")
      (libsource (lib "eagle-import") (part "MLCC0603"))
    )
    (comp (ref "C417")
      (value "220n 25v")
      (footprint "eagle-import:0603_WAVE")
      (libsource (lib "eagle-import") (part "MLCC0603"))
    )
    (comp (ref "C418")
      (value "220n 25v")
      (footprint "eagle-import:0603_WAVE")
      (libsource (lib "eagle-import") (part "MLCC0603"))
    )
    (comp (ref "C419")
      (value "220n 25v")
      (footprint "eagle-import:0603_WAVE")
      (libsource (lib "eagle-import") (part "MLCC0603"))
    )
    (comp (ref "C420")
      (value "220n 25v")
      (footprint "eagle-import:0603_WAVE")
      (libsource (lib "eagle-import") (part "MLCC0603"))
    )
    (comp (ref "C421")
      (value "100n 25v")
      (footprint "eagle-import:0603_WAVE")
      (libsource (lib "eagle-import") (part "MLCC0603"))
    )
    (comp (ref "C422")
      (value "100n")
      (footprint "eagle-import:0603_WAVE")
      (libsource (lib "eagle-import") (part "MLCC0603"))
    )
    (comp (ref "C423")
      (value "100n")
      (footprint "eagle-import:0603_WAVE")
      (libsource (lib "eagle-import") (part "MLCC0603"))
    )
    (comp (ref "C424")
      (value "10u 25v")
      (footprint "eagle-import:0603_WAVE")
      (libsource (lib "eagle-import") (part "MLCC0603"))
    )
    (comp (ref "C425")
      (value "100p")
      (footprint "eagle-import:0603_WAVE")
      (libsource (lib "eagle-import") (part "MLCC0603"))
    )
    (comp (ref "C426")
      (value "100n")
      (footprint "eagle-import:0603_WAVE")
      (libsource (lib "eagle-import") (part "MLCC0603"))
    )
    (comp (ref "C427")
      (value "100n")
      (footprint "eagle-import:0603_WAVE")
      (libsource (lib "eagle-import") (part "MLCC0603"))
    )
    (comp (ref "C428")
      (value "100n")
      (footprint "eagle-import:0603_WAVE")
      (libsource (lib "eagle-import") (part "MLCC0603"))
    )
    (comp (ref "C429")
      (value "100n")
      (footprint "eagle-import:0603_WAVE")
      (libsource (lib "eagle-import") (part "MLCC0603"))
    )
    (comp (ref "C430")
      (value "100n")
      (footprint "eagle-import:0603_WAVE")
      (libsource (lib "eagle-import") (part "MLCC0603"))
    )
    (comp (ref "C431")
      (value "100n")
      (footprint "eagle-import:0603_WAVE")
      (libsource (lib "eagle-import") (part "MLCC0603"))
    )
    (comp (ref "C432")
      (value "100p")
      (footprint "eagle-import:0603_WAVE")
      (libsource (lib "eagle-import") (part "MLCC0603"))
    )
    (comp (ref "D401")
      (value "DSK24")
      (footprint "eagle-import:SOD-123")
      (libsource (lib "eagle-import") (part "DSK24"))
    )
    (comp (ref "D402")
      (value "DSK24")
      (footprint "eagle-import:SOD-123")
      (libsource (lib "eagle-import") (part "DSK24"))
    )
    (comp (ref "D403")
      (value "DSK24")
      (footprint "eagle-import:SOD-123")
      (libsource (lib "eagle-import") (part "DSK24"))
    )
    (comp (ref "D404")
      (value "DSK24")
      (footprint "eagle-import:SOD-123")
      (libsource (lib "eagle-import") (part "DSK24"))
    )
    (comp (ref "J401")
      (value "4P-6.35P")
      (footprint "eagle-import:4P-6.35P")
      (libsource (lib "eagle-import") (part "4P-6.35P"))
    )
    (comp (ref "J402")
      (value "SH-2")
      (footprint "eagle-import:SM02B-SSR-H-TB")
      (libsource (lib "eagle-import") (part "SH-2"))
    )
    (comp (ref "J403")
      (value "2P-6.35P")
      (footprint "eagle-import:2P-6.35P")
      (libsource (lib "eagle-import") (part "2P-6.35P"))
    )
    (comp (ref "P401")
      (value "POWPAD")
      (footprint "eagle-import:TH-HP")
      (libsource (lib "eagle-import") (part "POWPAD"))
    )
    (comp (ref "P402")
      (value "POWPAD")
      (footprint "eagle-import:TH-HP")
      (libsource (lib "eagle-import") (part "POWPAD"))
    )
    (comp (ref "P403")
      (value "POWPAD")
      (footprint "eagle-import:TH-HP")
      (libsource (lib "eagle-import") (part "POWPAD"))
    )
    (comp (ref "P404")
      (value "POWPAD")
      (footprint "eagle-import:TH-HP")
      (libsource (lib "eagle-import") (part "POWPAD"))
    )
    (comp (ref "P405")
      (value "POWPAD")
      (footprint "eagle-import:TH-HP")
      (libsource (lib "eagle-import") (part "POWPAD"))
    )
    (comp (ref "P406")
      (value "POWPAD")
      (footprint "eagle-import:TH-HP")
      (libsource (lib "eagle-import") (part "POWPAD"))
    )
    (comp (ref "Q401")
      (value "IRF7580")
      (footprint "eagle-import:DIRECTFET-ME")
      (libsource (lib "eagle-import") (part "IRF7580"))
    )
    (comp (ref "Q402")
      (value "IRF7580")
      (footprint "eagle-import:DIRECTFET-ME")
      (libsource (lib "eagle-import") (part "IRF7580"))
    )
    (comp (ref "Q403")
      (value "IRF7580")
      (footprint "eagle-import:DIRECTFET-ME")
      (libsource (lib "eagle-import") (part "IRF7580"))
    )
    (comp (ref "Q404")
      (value "IRF7580")
      (footprint "eagle-import:DIRECTFET-ME")
      (libsource (lib "eagle-import") (part "IRF7580"))
    )
    (comp (ref "Q405")
      (value "IRF7580")
      (footprint "eagle-import:DIRECTFET-ME")
      (libsource (lib "eagle-import") (part "IRF7580"))
    )
    (comp (ref "Q406")
      (value "IRF7580")
      (footprint "eagle-import:DIRECTFET-ME")
      (libsource (lib "eagle-import") (part "IRF7580"))
    )
    (comp (ref "Q407")
      (value "IRF7580")
      (footprint "eagle-import:DIRECTFET-ME")
      (libsource (lib "eagle-import") (part "IRF7580"))
    )
    (comp (ref "Q408")
      (value "IRF7580")
      (footprint "eagle-import:DIRECTFET-ME")
      (libsource (lib "eagle-import") (part "IRF7580"))
    )
    (comp (ref "Q409")
      (value "IRF7580")
      (footprint "eagle-import:DIRECTFET-ME")
      (libsource (lib "eagle-import") (part "IRF7580"))
    )
    (comp (ref "R401")
      (value "10k")
      (footprint "eagle-import:0603_WAVE")
      (libsource (lib "eagle-import") (part "RESISTOR0603"))
    )
    (comp (ref "R402")
      (value "10k")
      (footprint "eagle-import:0603_WAVE")
      (libsource (lib "eagle-import") (part "RESISTOR0603"))
    )
    (comp (ref "R403")
      (value "10k")
      (footprint "eagle-import:0603_WAVE")
      (libsource (lib "eagle-import") (part "RESISTOR0603"))
    )
    (comp (ref "R404")
      (value "10k")
      (footprint "eagle-import:0603_WAVE")
      (libsource (lib "eagle-import") (part "RESISTOR0603"))
    )
    (comp (ref "R405")
      (value "10k")
      (footprint "eagle-import:0603_WAVE")
      (libsource (lib "eagle-import") (part "RESISTOR0603"))
    )
    (comp (ref "R406")
      (value "10k")
      (footprint "eagle-import:0603_WAVE")
      (libsource (lib "eagle-import") (part "RESISTOR0603"))
    )
    (comp (ref "R407")
      (value "10k")
      (footprint "eagle-import:0603_WAVE")
      (libsource (lib "eagle-import") (part "RESISTOR0603"))
    )
    (comp (ref "R408")
      (value "10k")
      (footprint "eagle-import:0603_WAVE")
      (libsource (lib "eagle-import") (part "RESISTOR0603"))
    )
    (comp (ref "R409")
      (value "2.2")
      (footprint "eagle-import:0603_WAVE")
      (libsource (lib "eagle-import") (part "RESISTOR0603"))
    )
    (comp (ref "R410")
      (value "2.2")
      (footprint "eagle-import:0603_WAVE")
      (libsource (lib "eagle-import") (part "RESISTOR0603"))
    )
    (comp (ref "R411")
      (value "2.2")
      (footprint "eagle-import:0603_WAVE")
      (libsource (lib "eagle-import") (part "RESISTOR0603"))
    )
    (comp (ref "R412")
      (value "2.2")
      (footprint "eagle-import:0603_WAVE")
      (libsource (lib "eagle-import") (part "RESISTOR0603"))
    )
    (comp (ref "R413")
      (value "2.2")
      (footprint "eagle-import:0603_WAVE")
      (libsource (lib "eagle-import") (part "RESISTOR0603"))
    )
    (comp (ref "R414")
      (value "2.2")
      (footprint "eagle-import:0603_WAVE")
      (libsource (lib "eagle-import") (part "RESISTOR0603"))
    )
    (comp (ref "R415")
      (value "2.2")
      (footprint "eagle-import:0603_WAVE")
      (libsource (lib "eagle-import") (part "RESISTOR0603"))
    )
    (comp (ref "R416")
      (value "2.2")
      (footprint "eagle-import:0603_WAVE")
      (libsource (lib "eagle-import") (part "RESISTOR0603"))
    )
    (comp (ref "R417")
      (value "2.2")
      (footprint "eagle-import:0603_WAVE")
      (libsource (lib "eagle-import") (part "RESISTOR0603"))
    )
    (comp (ref "R418")
      (value "2.2")
      (footprint "eagle-import:0603_WAVE")
      (libsource (lib "eagle-import") (part "RESISTOR0603"))
    )
    (comp (ref "R419")
      (value "2.2")
      (footprint "eagle-import:0603_WAVE")
      (libsource (lib "eagle-import") (part "RESISTOR0603"))
    )
    (comp (ref "R420")
      (value "2.2")
      (footprint "eagle-import:0603_WAVE")
      (libsource (lib "eagle-import") (part "RESISTOR0603"))
    )
    (comp (ref "R421")
      (value "700u")
      (footprint "eagle-import:3920")
      (libsource (lib "eagle-import") (part "LRMAP3920"))
    )
    (comp (ref "R422")
      (value "700u")
      (footprint "eagle-import:3920")
      (libsource (lib "eagle-import") (part "LRMAP3920"))
    )
    (comp (ref "R423")
      (value "100")
      (footprint "eagle-import:0603_WAVE")
      (libsource (lib "eagle-import") (part "RESISTOR0603"))
    )
    (comp (ref "R424")
      (value "100")
      (footprint "eagle-import:0603_WAVE")
      (libsource (lib "eagle-import") (part "RESISTOR0603"))
    )
    (comp (ref "R425")
      (value "100")
      (footprint "eagle-import:0603_WAVE")
      (libsource (lib "eagle-import") (part "RESISTOR0603"))
    )
    (comp (ref "R426")
      (value "100")
      (footprint "eagle-import:0603_WAVE")
      (libsource (lib "eagle-import") (part "RESISTOR0603"))
    )
    (comp (ref "R427")
      (value "100k")
      (footprint "eagle-import:0603_WAVE")
      (libsource (lib "eagle-import") (part "NTC0603"))
    )
    (comp (ref "R428")
      (value "1k13")
      (footprint "eagle-import:0603_WAVE")
      (libsource (lib "eagle-import") (part "RESISTOR0603"))
    )
    (comp (ref "R429")
      (value "220")
      (footprint "eagle-import:0603_WAVE")
      (libsource (lib "eagle-import") (part "RESISTOR0603"))
    )
    (comp (ref "R430")
      (value "10k")
      (footprint "eagle-import:0603_WAVE")
      (libsource (lib "eagle-import") (part "RESISTOR0603"))
    )
    (comp (ref "R431")
      (value "2.2")
      (footprint "eagle-import:0603_WAVE")
      (libsource (lib "eagle-import") (part "RESISTOR0603"))
    )
    (comp (ref "U401")
      (value "SI82397")
      (footprint "eagle-import:SOIC-16-WB")
      (libsource (lib "eagle-import") (part "SI82397"))
    )
    (comp (ref "U402")
      (value "SI82397")
      (footprint "eagle-import:SOIC-16-WB")
      (libsource (lib "eagle-import") (part "SI82397"))
    )
    (comp (ref "U403")
      (value "SI82397")
      (footprint "eagle-import:SOIC-16-WB")
      (libsource (lib "eagle-import") (part "SI82397"))
    )
    (comp (ref "U404")
      (value "SI82397")
      (footprint "eagle-import:SOIC-16-WB")
      (libsource (lib "eagle-import") (part "SI82397"))
    )
    (comp (ref "U405")
      (value "AD8418A")
      (footprint "eagle-import:MSOP-8")
      (libsource (lib "eagle-import") (part "AD8418A"))
    )
    (comp (ref "U406")
      (value "AD8418A")
      (footprint "eagle-import:MSOP-8")
      (libsource (lib "eagle-import") (part "AD8418A"))
    )
    (comp (ref "U407")
      (value "SI8261")
      (footprint "eagle-import:SOIC_8")
      (libsource (lib "eagle-import") (part "SI8261"))
    )
  )
  (nets
    (net (code "1") (name "1.8V") (class "Default")
      (node (ref "C103") (pin "P$1") (pinfunction "P$1_P$1") (pintype "bidirectional"))
      (node (ref "C105") (pin "P$1") (pinfunction "P$1_P$1") (pintype "bidirectional"))
      (node (ref "C107") (pin "P$1") (pinfunction "P$1_P$1") (pintype "bidirectional"))
      (node (ref "U102") (pin "15") (pinfunction "VCC_CORE_15") (pintype "bidirectional"))
      (node (ref "U102") (pin "45") (pinfunction "VCC_CORE_45") (pintype "bidirectional"))
      (node (ref "U102") (pin "63") (pinfunction "VCC_CORE_63") (pintype "bidirectional"))
    )
    (net (code "2") (name "3.3V") (class "Default")
      (node (ref "C101") (pin "P$1") (pinfunction "P$1_P$1") (pintype "bidirectional"))
      (node (ref "C102") (pin "P$1") (pinfunction "P$1_P$1") (pintype "bidirectional"))
      (node (ref "C104") (pin "P$1") (pinfunction "P$1_P$1") (pintype "bidirectional"))
      (node (ref "C106") (pin "P$1") (pinfunction "P$1_P$1") (pintype "bidirectional"))
      (node (ref "C108") (pin "P$1") (pinfunction "P$1_P$1") (pintype "bidirectional"))
      (node (ref "C109") (pin "P$1") (pinfunction "P$1_P$1") (pintype "bidirectional"))
      (node (ref "C110") (pin "P$1") (pinfunction "P$1_P$1") (pintype "bidirectional"))
      (node (ref "C111") (pin "P$1") (pinfunction "P$1_P$1") (pintype "bidirectional"))
      (node (ref "C214") (pin "P$1") (pinfunction "P$1_P$1") (pintype "bidirectional"))
      (node (ref "C215") (pin "P$1") (pinfunction "P$1_P$1") (pintype "bidirectional"))
      (node (ref "C216") (pin "P$1") (pinfunction "P$1_P$1") (pintype "bidirectional"))
      (node (ref "C217") (pin "P$1") (pinfunction "P$1_P$1") (pintype "bidirectional"))
      (node (ref "C309") (pin "P$1") (pinfunction "P$1_P$1") (pintype "bidirectional"))
      (node (ref "C405") (pin "P$1") (pinfunction "P$1_P$1") (pintype "bidirectional"))
      (node (ref "C407") (pin "P$1") (pinfunction "P$1_P$1") (pintype "bidirectional"))
      (node (ref "C409") (pin "P$1") (pinfunction "P$1_P$1") (pintype "bidirectional"))
      (node (ref "C411") (pin "P$1") (pinfunction "P$1_P$1") (pintype "bidirectional"))
      (node (ref "C413") (pin "P$1") (pinfunction "P$1_P$1") (pintype "bidirectional"))
      (node (ref "C414") (pin "P$1") (pinfunction "P$1_P$1") (pintype "bidirectional"))
      (node (ref "C415") (pin "P$1") (pinfunction "P$1_P$1") (pintype "bidirectional"))
      (node (ref "C416") (pin "P$1") (pinfunction "P$1_P$1") (pintype "bidirectional"))
      (node (ref "C501") (pin "P$1") (pinfunction "P$1_P$1") (pintype "bidirectional"))
      (node (ref "C502") (pin "P$1") (pinfunction "P$1_P$1") (pintype "bidirectional"))
      (node (ref "D504") (pin "P$2") (pinfunction "2_P$2") (pintype "bidirectional"))
      (node (ref "D505") (pin "P$2") (pinfunction "2_P$2") (pintype "bidirectional"))
      (node (ref "D506") (pin "P$2") (pinfunction "2_P$2") (pintype "bidirectional"))
      (node (ref "J505") (pin "1") (pinfunction "S_1") (pintype "passive"))
      (node (ref "R101") (pin "P$2") (pinfunction "P$2_P$2") (pintype "bidirectional"))
      (node (ref "R102") (pin "P$1") (pinfunction "P$1_P$1") (pintype "bidirectional"))
      (node (ref "R501") (pin "P$1") (pinfunction "P$1_P$1") (pintype "bidirectional"))
      (node (ref "R502") (pin "P$2") (pinfunction "P$2_P$2") (pintype "bidirectional"))
      (node (ref "R503") (pin "P$2") (pinfunction "P$2_P$2") (pintype "bidirectional"))
      (node (ref "U101") (pin "6") (pinfunction "VDD_6") (pintype "bidirectional"))
      (node (ref "U102") (pin "13") (pinfunction "VCC_13") (pintype "bidirectional"))
      (node (ref "U102") (pin "2") (pinfunction "VCC_2") (pintype "bidirectional"))
      (node (ref "U102") (pin "43") (pinfunction "VCC_43") (pintype "bidirectional"))
      (node (ref "U102") (pin "52") (pinfunction "PLL_VCC_52") (pintype "bidirectional"))
      (node (ref "U102") (pin "61") (pinfunction "VCC_61") (pintype "bidirectional"))
      (node (ref "U102") (pin "72") (pinfunction "VCC_72") (pintype "bidirectional"))
      (node (ref "U205") (pin "8") (pinfunction "VCC_8") (pintype "bidirectional"))
      (node (ref "U206") (pin "8") (pinfunction "VCC_8") (pintype "bidirectional"))
      (node (ref "U207") (pin "8") (pinfunction "VCC_8") (pintype "bidirectional"))
      (node (ref "U208") (pin "8") (pinfunction "VCC_8") (pintype "bidirectional"))
      (node (ref "U302") (pin "3") (pinfunction "VOUT_3") (pintype "bidirectional"))
      (node (ref "U401") (pin "3") (pinfunction "VDDI_3") (pintype "bidirectional"))
      (node (ref "U401") (pin "8") (pinfunction "VDDI_8") (pintype "bidirectional"))
      (node (ref "U402") (pin "3") (pinfunction "VDDI_3") (pintype "bidirectional"))
      (node (ref "U402") (pin "8") (pinfunction "VDDI_8") (pintype "bidirectional"))
      (node (ref "U403") (pin "3") (pinfunction "VDDI_3") (pintype "bidirectional"))
      (node (ref "U403") (pin "8") (pinfunction "VDDI_8") (pintype "bidirectional"))
      (node (ref "U404") (pin "3") (pinfunction "VDDI_3") (pintype "bidirectional"))
      (node (ref "U404") (pin "8") (pinfunction "VDDI_8") (pintype "bidirectional"))
      (node (ref "U501") (pin "5") (pinfunction "VIO_5") (pintype "bidirectional"))
      (node (ref "U501") (pin "6") (pinfunction "VDD_6") (pintype "bidirectional"))
      (node (ref "U501") (pin "7") (pinfunction "VREGIN_7") (pintype "bidirectional"))
    )
    (net (code "3") (name "5V") (class "Default")
      (node (ref "C112") (pin "P$1") (pinfunction "P$1_P$1") (pintype "bidirectional"))
      (node (ref "C113") (pin "P$1") (pinfunction "P$1_P$1") (pintype "bidirectional"))
      (node (ref "C201") (pin "P$1") (pinfunction "P$1_P$1") (pintype "bidirectional"))
      (node (ref "C202") (pin "P$1") (pinfunction "P$1_P$1") (pintype "bidirectional"))
      (node (ref "C203") (pin "P$1") (pinfunction "P$1_P$1") (pintype "bidirectional"))
      (node (ref "C204") (pin "P$1") (pinfunction "P$1_P$1") (pintype "bidirectional"))
      (node (ref "C205") (pin "P$1") (pinfunction "P$1_P$1") (pintype "bidirectional"))
      (node (ref "C222") (pin "P$1") (pinfunction "P$1_P$1") (pintype "bidirectional"))
      (node (ref "C223") (pin "P$1") (pinfunction "P$1_P$1") (pintype "bidirectional"))
      (node (ref "C224") (pin "P$1") (pinfunction "P$1_P$1") (pintype "bidirectional"))
      (node (ref "C225") (pin "P$1") (pinfunction "P$1_P$1") (pintype "bidirectional"))
      (node (ref "C310") (pin "P$1") (pinfunction "P$1_P$1") (pintype "bidirectional"))
      (node (ref "C422") (pin "P$1") (pinfunction "P$1_P$1") (pintype "bidirectional"))
      (node (ref "C423") (pin "P$1") (pinfunction "P$1_P$1") (pintype "bidirectional"))
      (node (ref "D101") (pin "P$2") (pinfunction "2_P$2") (pintype "bidirectional"))
      (node (ref "D201") (pin "P$2") (pinfunction "2_P$2") (pintype "bidirectional"))
      (node (ref "D202") (pin "P$2") (pinfunction "2_P$2") (pintype "bidirectional"))
      (node (ref "D203") (pin "P$2") (pinfunction "2_P$2") (pintype "bidirectional"))
      (node (ref "J201") (pin "1") (pinfunction "S_1") (pintype "passive"))
      (node (ref "J202") (pin "1") (pinfunction "S_1") (pintype "passive"))
      (node (ref "J203") (pin "1") (pinfunction "S_1") (pintype "passive"))
      (node (ref "J204") (pin "1") (pinfunction "S_1") (pintype "passive"))
      (node (ref "J205") (pin "1") (pinfunction "S_1") (pintype "passive"))
      (node (ref "J402") (pin "1") (pinfunction "S_1") (pintype "passive"))
      (node (ref "R103") (pin "P$2") (pinfunction "P$2_P$2") (pintype "bidirectional"))
      (node (ref "R106") (pin "P$2") (pinfunction "P$2_P$2") (pintype "bidirectional"))
      (node (ref "R109") (pin "P$2") (pinfunction "P$2_P$2") (pintype "bidirectional"))
      (node (ref "R117") (pin "P$2") (pinfunction "P$2_P$2") (pintype "bidirectional"))
      (node (ref "R120") (pin "P$2") (pinfunction "P$2_P$2") (pintype "bidirectional"))
      (node (ref "R214") (pin "P$1") (pinfunction "P$1_P$1") (pintype "bidirectional"))
      (node (ref "R215") (pin "P$1") (pinfunction "P$1_P$1") (pintype "bidirectional"))
      (node (ref "R216") (pin "P$1") (pinfunction "P$1_P$1") (pintype "bidirectional"))
      (node (ref "R217") (pin "P$1") (pinfunction "P$1_P$1") (pintype "bidirectional"))
      (node (ref "R219") (pin "P$1") (pinfunction "P$1_P$1") (pintype "bidirectional"))
      (node (ref "R220") (pin "P$1") (pinfunction "P$1_P$1") (pintype "bidirectional"))
      (node (ref "R221") (pin "P$1") (pinfunction "P$1_P$1") (pintype "bidirectional"))
      (node (ref "R222") (pin "P$1") (pinfunction "P$1_P$1") (pintype "bidirectional"))
      (node (ref "R223") (pin "P$1") (pinfunction "P$1_P$1") (pintype "bidirectional"))
      (node (ref "R224") (pin "P$1") (pinfunction "P$1_P$1") (pintype "bidirectional"))
      (node (ref "R225") (pin "P$1") (pinfunction "P$1_P$1") (pintype "bidirectional"))
      (node (ref "R226") (pin "P$1") (pinfunction "P$1_P$1") (pintype "bidirectional"))
      (node (ref "R427") (pin "P$2") (pinfunction "P$2_P$2") (pintype "bidirectional"))
      (node (ref "U102") (pin "23") (pinfunction "V5_23") (pintype "bidirectional"))
      (node (ref "U201") (pin "5") (pinfunction "VCC_5") (pintype "bidirectional"))
      (node (ref "U202") (pin "5") (pinfunction "VCC_5") (pintype "bidirectional"))
      (node (ref "U203") (pin "5") (pinfunction "VCC_5") (pintype "bidirectional"))
      (node (ref "U204") (pin "5") (pinfunction "VCC_5") (pintype "bidirectional"))
      (node (ref "U303") (pin "3") (pinfunction "VOUT_3") (pintype "bidirectional"))
      (node (ref "U405") (pin "6") (pinfunction "P$1_6") (pintype "bidirectional"))
      (node (ref "U405") (pin "7") (pinfunction "P$1_7") (pintype "bidirectional"))
      (node (ref "U406") (pin "6") (pinfunction "P$1_6") (pintype "bidirectional"))
      (node (ref "U406") (pin "7") (pinfunction "P$1_7") (pintype "bidirectional"))
    )
    (net (code "4") (name "12V") (class "Default")
      (node (ref "C301") (pin "P$1") (pinfunction "P$1_P$1") (pintype "bidirectional"))
      (node (ref "C302") (pin "+") (pinfunction "AN_+") (pintype "bidirectional"))
      (node (ref "C401") (pin "P$1") (pinfunction "P$1_P$1") (pintype "bidirectional"))
      (node (ref "C402") (pin "P$1") (pinfunction "P$1_P$1") (pintype "bidirectional"))
      (node (ref "C403") (pin "P$1") (pinfunction "P$1_P$1") (pintype "bidirectional"))
      (node (ref "C404") (pin "P$1") (pinfunction "P$1_P$1") (pintype "bidirectional"))
      (node (ref "C406") (pin "P$1") (pinfunction "P$1_P$1") (pintype "bidirectional"))
      (node (ref "C408") (pin "P$1") (pinfunction "P$1_P$1") (pintype "bidirectional"))
      (node (ref "C410") (pin "P$1") (pinfunction "P$1_P$1") (pintype "bidirectional"))
      (node (ref "C412") (pin "P$1") (pinfunction "P$1_P$1") (pintype "bidirectional"))
      (node (ref "C421") (pin "P$1") (pinfunction "P$1_P$1") (pintype "bidirectional"))
      (node (ref "C424") (pin "P$1") (pinfunction "P$1_P$1") (pintype "bidirectional"))
      (node (ref "J301") (pin "2") (pinfunction "S_2") (pintype "passive"))
      (node (ref "R301") (pin "P$2") (pinfunction "P$2_P$2") (pintype "bidirectional"))
      (node (ref "R409") (pin "P$1") (pinfunction "P$1_P$1") (pintype "bidirectional"))
      (node (ref "R410") (pin "P$1") (pinfunction "P$1_P$1") (pintype "bidirectional"))
      (node (ref "R411") (pin "P$1") (pinfunction "P$1_P$1") (pintype "bidirectional"))
      (node (ref "R412") (pin "P$1") (pinfunction "P$1_P$1") (pintype "bidirectional"))
      (node (ref "U301") (pin "5") (pinfunction "IN_5") (pintype "bidirectional"))
      (node (ref "U401") (pin "11") (pinfunction "VDDB_11") (pintype "bidirectional"))
      (node (ref "U402") (pin "11") (pinfunction "VDDB_11") (pintype "bidirectional"))
      (node (ref "U403") (pin "11") (pinfunction "VDDB_11") (pintype "bidirectional"))
      (node (ref "U404") (pin "11") (pinfunction "VDDB_11") (pintype "bidirectional"))
      (node (ref "U407") (pin "8") (pinfunction "VDD_8") (pintype "bidirectional"))
    )
    (net (code "5") (name "ADC_I0_U_PF") (class "Default")
      (node (ref "R113") (pin "P$2") (pinfunction "P$2_P$2") (pintype "bidirectional"))
      (node (ref "U405") (pin "5") (pinfunction "O_5") (pintype "bidirectional"))
    )
    (net (code "6") (name "ADC_I1_V_PF") (class "Default")
      (node (ref "R115") (pin "P$2") (pinfunction "P$2_P$2") (pintype "bidirectional"))
      (node (ref "U406") (pin "5") (pinfunction "O_5") (pintype "bidirectional"))
    )
    (net (code "7") (name "ADC_T_MOSFETS") (class "Default")
      (node (ref "C425") (pin "P$1") (pinfunction "P$1_P$1") (pintype "bidirectional"))
      (node (ref "R111") (pin "P$2") (pinfunction "P$2_P$2") (pintype "bidirectional"))
      (node (ref "R427") (pin "P$1") (pinfunction "P$1_P$1") (pintype "bidirectional"))
      (node (ref "R428") (pin "P$2") (pinfunction "P$2_P$2") (pintype "bidirectional"))
    )
    (net (code "8") (name "ADC_T_MOTOR") (class "Default")
      (node (ref "C432") (pin "P$1") (pinfunction "P$1_P$1") (pintype "bidirectional"))
      (node (ref "J402") (pin "2") (pinfunction "S_2") (pintype "passive"))
      (node (ref "R112") (pin "P$1") (pinfunction "P$1_P$1") (pintype "bidirectional"))
      (node (ref "R430") (pin "P$2") (pinfunction "P$2_P$2") (pintype "bidirectional"))
    )
    (net (code "9") (name "AENC_UX_P") (class "Default")
      (node (ref "C226") (pin "P$1") (pinfunction "P$1_P$1") (pintype "bidirectional"))
      (node (ref "D201") (pin "P$3") (pinfunction "3_P$3") (pintype "bidirectional"))
      (node (ref "R213") (pin "P$2") (pinfunction "P$2_P$2") (pintype "bidirectional"))
      (node (ref "U102") (pin "25") (pinfunction "AENC_UX_POS_25") (pintype "bidirectional"))
    )
    (net (code "10") (name "AENC_VN_P") (class "Default")
      (node (ref "C227") (pin "P$1") (pinfunction "P$1_P$1") (pintype "bidirectional"))
      (node (ref "D202") (pin "P$3") (pinfunction "3_P$3") (pintype "bidirectional"))
      (node (ref "R218") (pin "P$2") (pinfunction "P$2_P$2") (pintype "bidirectional"))
      (node (ref "U102") (pin "27") (pinfunction "AENC_VN_POS_27") (pintype "bidirectional"))
    )
    (net (code "11") (name "AENC_WY_P") (class "Default")
      (node (ref "C228") (pin "P$1") (pinfunction "P$1_P$1") (pintype "bidirectional"))
      (node (ref "D203") (pin "P$3") (pinfunction "3_P$3") (pintype "bidirectional"))
      (node (ref "R227") (pin "P$2") (pinfunction "P$2_P$2") (pintype "bidirectional"))
      (node (ref "U102") (pin "29") (pinfunction "AENC_WY_POS_29") (pintype "bidirectional"))
    )
    (net (code "12") (name "BRAKE") (class "Default")
      (node (ref "R429") (pin "P$2") (pinfunction "P$2_P$2") (pintype "bidirectional"))
      (node (ref "U102") (pin "31") (pinfunction "BRAKE_31") (pintype "bidirectional"))
    )
    (net (code "13") (name "CP2102_RX") (class "Default")
      (node (ref "J502") (pin "2") (pinfunction "S_2") (pintype "passive"))
      (node (ref "JP505") (pin "2") (pinfunction "2_2") (pintype "passive"))
      (node (ref "U102") (pin "11") (pinfunction "TXD_SYNCO_11") (pintype "bidirectional"))
    )
    (net (code "14") (name "CP2102_TX") (class "Default")
      (node (ref "J502") (pin "1") (pinfunction "S_1") (pintype "passive"))
      (node (ref "JP506") (pin "2") (pinfunction "2_2") (pintype "passive"))
      (node (ref "U102") (pin "10") (pinfunction "RXD_SYNCI_10") (pintype "bidirectional"))
    )
    (net (code "15") (name "D+") (class "Default")
      (node (ref "D503") (pin "3") (pinfunction "3_3") (pintype "bidirectional"))
      (node (ref "J503") (pin "D+") (pinfunction "D+_D+") (pintype "bidirectional"))
      (node (ref "U501") (pin "3") (pinfunction "D+_3") (pintype "bidirectional"))
    )
    (net (code "16") (name "D-") (class "Default")
      (node (ref "D503") (pin "2") (pinfunction "2_2") (pintype "bidirectional"))
      (node (ref "J503") (pin "D-") (pinfunction "D-_D-") (pintype "bidirectional"))
      (node (ref "U501") (pin "4") (pinfunction "D-_4") (pintype "bidirectional"))
    )
    (net (code "17") (name "DBG_SPI_MISO") (class "Default")
      (node (ref "J505") (pin "9") (pinfunction "S_9") (pintype "passive"))
      (node (ref "U102") (pin "4") (pinfunction "GPIO6_4") (pintype "bidirectional"))
    )
    (net (code "18") (name "DBG_SPI_MOSI") (class "Default")
      (node (ref "J505") (pin "7") (pinfunction "S_7") (pintype "passive"))
      (node (ref "U102") (pin "1") (pinfunction "GPIO5_1") (pintype "bidirectional"))
    )
    (net (code "19") (name "DBG_SPI_NSCS") (class "Default")
      (node (ref "J505") (pin "3") (pinfunction "S_3") (pintype "passive"))
      (node (ref "U102") (pin "75") (pinfunction "GPIO3_75") (pintype "bidirectional"))
    )
    (net (code "20") (name "DBG_SPI_SCK") (class "Default")
      (node (ref "J505") (pin "5") (pinfunction "S_5") (pintype "passive"))
      (node (ref "U102") (pin "76") (pinfunction "GPIO4_76") (pintype "bidirectional"))
    )
    (net (code "21") (name "DBG_SPI_TRG") (class "Default")
      (node (ref "J505") (pin "4") (pinfunction "S_4") (pintype "passive"))
      (node (ref "U102") (pin "5") (pinfunction "GPIO7_5") (pintype "bidirectional"))
    )
    (net (code "22") (name "DCBUS") (class "Default")
      (node (ref "C303") (pin "+") (pinfunction "AN_+") (pintype "bidirectional"))
      (node (ref "C304") (pin "+") (pinfunction "AN_+") (pintype "bidirectional"))
      (node (ref "C306") (pin "+") (pinfunction "AN_+") (pintype "bidirectional"))
      (node (ref "C308") (pin "+") (pinfunction "AN_+") (pintype "bidirectional"))
      (node (ref "J302") (pin "1") (pinfunction "S_1") (pintype "passive"))
      (node (ref "J403") (pin "1") (pinfunction "S_1") (pintype "passive"))
      (node (ref "P301") (pin "H1") (pinfunction "S_H1") (pintype "passive"))
      (node (ref "P301") (pin "H10") (pinfunction "S_H10") (pintype "passive"))
      (node (ref "P301") (pin "H11") (pinfunction "S_H11") (pintype "passive"))
      (node (ref "P301") (pin "H12") (pinfunction "S_H12") (pintype "passive"))
      (node (ref "P301") (pin "H2") (pinfunction "S_H2") (pintype "passive"))
      (node (ref "P301") (pin "H3") (pinfunction "S_H3") (pintype "passive"))
      (node (ref "P301") (pin "H4") (pinfunction "S_H4") (pintype "passive"))
      (node (ref "P301") (pin "H5") (pinfunction "S_H5") (pintype "passive"))
      (node (ref "P301") (pin "H6") (pinfunction "S_H6") (pintype "passive"))
      (node (ref "P301") (pin "H7") (pinfunction "S_H7") (pintype "passive"))
      (node (ref "P301") (pin "H8") (pinfunction "S_H8") (pintype "passive"))
      (node (ref "P301") (pin "H9") (pinfunction "S_H9") (pintype "passive"))
      (node (ref "P301") (pin "PAD") (pinfunction "S_PAD") (pintype "passive"))
      (node (ref "P405") (pin "H1") (pinfunction "S_H1") (pintype "passive"))
      (node (ref "P405") (pin "H10") (pinfunction "S_H10") (pintype "passive"))
      (node (ref "P405") (pin "H11") (pinfunction "S_H11") (pintype "passive"))
      (node (ref "P405") (pin "H12") (pinfunction "S_H12") (pintype "passive"))
      (node (ref "P405") (pin "H2") (pinfunction "S_H2") (pintype "passive"))
      (node (ref "P405") (pin "H3") (pinfunction "S_H3") (pintype "passive"))
      (node (ref "P405") (pin "H4") (pinfunction "S_H4") (pintype "passive"))
      (node (ref "P405") (pin "H5") (pinfunction "S_H5") (pintype "passive"))
      (node (ref "P405") (pin "H6") (pinfunction "S_H6") (pintype "passive"))
      (node (ref "P405") (pin "H7") (pinfunction "S_H7") (pintype "passive"))
      (node (ref "P405") (pin "H8") (pinfunction "S_H8") (pintype "passive"))
      (node (ref "P405") (pin "H9") (pinfunction "S_H9") (pintype "passive"))
      (node (ref "P405") (pin "PAD") (pinfunction "S_PAD") (pintype "passive"))
      (node (ref "Q401") (pin "D1") (pinfunction "D1_D1") (pintype "bidirectional"))
      (node (ref "Q401") (pin "D2") (pinfunction "D1_D2") (pintype "bidirectional"))
      (node (ref "Q401") (pin "D3") (pinfunction "D1_D3") (pintype "bidirectional"))
      (node (ref "Q401") (pin "D4") (pinfunction "D1_D4") (pintype "bidirectional"))
      (node (ref "Q402") (pin "D1") (pinfunction "D1_D1") (pintype "bidirectional"))
      (node (ref "Q402") (pin "D2") (pinfunction "D1_D2") (pintype "bidirectional"))
      (node (ref "Q402") (pin "D3") (pinfunction "D1_D3") (pintype "bidirectional"))
      (node (ref "Q402") (pin "D4") (pinfunction "D1_D4") (pintype "bidirectional"))
      (node (ref "Q403") (pin "D1") (pinfunction "D1_D1") (pintype "bidirectional"))
      (node (ref "Q403") (pin "D2") (pinfunction "D1_D2") (pintype "bidirectional"))
      (node (ref "Q403") (pin "D3") (pinfunction "D1_D3") (pintype "bidirectional"))
      (node (ref "Q403") (pin "D4") (pinfunction "D1_D4") (pintype "bidirectional"))
      (node (ref "Q404") (pin "D1") (pinfunction "D1_D1") (pintype "bidirectional"))
      (node (ref "Q404") (pin "D2") (pinfunction "D1_D2") (pintype "bidirectional"))
      (node (ref "Q404") (pin "D3") (pinfunction "D1_D3") (pintype "bidirectional"))
      (node (ref "Q404") (pin "D4") (pinfunction "D1_D4") (pintype "bidirectional"))
      (node (ref "R119") (pin "P$2") (pinfunction "P$2_P$2") (pintype "bidirectional"))
    )
    (net (code "23") (name "DIR") (class "Default")
      (node (ref "D505") (pin "P$3") (pinfunction "3_P$3") (pintype "bidirectional"))
      (node (ref "R508") (pin "P$2") (pinfunction "P$2_P$2") (pintype "bidirectional"))
      (node (ref "R511") (pin "P$2") (pinfunction "P$2_P$2") (pintype "bidirectional"))
      (node (ref "U102") (pin "56") (pinfunction "DIR_56") (pintype "bidirectional"))
    )
    (net (code "24") (name "ENC2_A") (class "Default")
      (node (ref "U102") (pin "64") (pinfunction "ENC2_A_64") (pintype "bidirectional"))
      (node (ref "U206") (pin "7") (pinfunction "Y_7") (pintype "output"))
    )
    (net (code "25") (name "ENC2_B") (class "Default")
      (node (ref "U102") (pin "65") (pinfunction "ENC2_B_65") (pintype "bidirectional"))
      (node (ref "U206") (pin "5") (pinfunction "Y_5") (pintype "output"))
    )
    (net (code "26") (name "ENC2_N") (class "Default")
      (node (ref "U102") (pin "66") (pinfunction "ENC2_N_66") (pintype "bidirectional"))
      (node (ref "U206") (pin "2") (pinfunction "Y_2") (pintype "output"))
    )
    (net (code "27") (name "ENC_A") (class "Default")
      (node (ref "U102") (pin "35") (pinfunction "ENC_A_35") (pintype "bidirectional"))
      (node (ref "U205") (pin "7") (pinfunction "Y_7") (pintype "output"))
    )
    (net (code "28") (name "ENC_B") (class "Default")
      (node (ref "U102") (pin "34") (pinfunction "ENC_B_34") (pintype "bidirectional"))
      (node (ref "U205") (pin "5") (pinfunction "Y_5") (pintype "output"))
    )
    (net (code "29") (name "ENC_N") (class "Default")
      (node (ref "U102") (pin "33") (pinfunction "ENC_N_33") (pintype "bidirectional"))
      (node (ref "U205") (pin "2") (pinfunction "Y_2") (pintype "output"))
    )
    (net (code "30") (name "ENO") (class "Default")
      (node (ref "R114") (pin "P$1") (pinfunction "P$1_P$1") (pintype "bidirectional"))
      (node (ref "U102") (pin "32") (pinfunction "ENO_32") (pintype "bidirectional"))
      (node (ref "U401") (pin "5") (pinfunction "EN_5") (pintype "bidirectional"))
      (node (ref "U402") (pin "5") (pinfunction "EN_5") (pintype "bidirectional"))
      (node (ref "U403") (pin "5") (pinfunction "EN_5") (pintype "bidirectional"))
      (node (ref "U404") (pin "5") (pinfunction "EN_5") (pintype "bidirectional"))
    )
    (net (code "31") (name "GND") (class "Default")
      (node (ref "C101") (pin "P$2") (pinfunction "P$2_P$2") (pintype "bidirectional"))
      (node (ref "C102") (pin "P$2") (pinfunction "P$2_P$2") (pintype "bidirectional"))
      (node (ref "C103") (pin "P$2") (pinfunction "P$2_P$2") (pintype "bidirectional"))
      (node (ref "C104") (pin "P$2") (pinfunction "P$2_P$2") (pintype "bidirectional"))
      (node (ref "C105") (pin "P$2") (pinfunction "P$2_P$2") (pintype "bidirectional"))
      (node (ref "C106") (pin "P$2") (pinfunction "P$2_P$2") (pintype "bidirectional"))
      (node (ref "C107") (pin "P$2") (pinfunction "P$2_P$2") (pintype "bidirectional"))
      (node (ref "C108") (pin "P$2") (pinfunction "P$2_P$2") (pintype "bidirectional"))
      (node (ref "C109") (pin "P$2") (pinfunction "P$2_P$2") (pintype "bidirectional"))
      (node (ref "C110") (pin "P$2") (pinfunction "P$2_P$2") (pintype "bidirectional"))
      (node (ref "C111") (pin "P$2") (pinfunction "P$2_P$2") (pintype "bidirectional"))
      (node (ref "C112") (pin "P$2") (pinfunction "P$2_P$2") (pintype "bidirectional"))
      (node (ref "C113") (pin "P$2") (pinfunction "P$2_P$2") (pintype "bidirectional"))
      (node (ref "C114") (pin "P$2") (pinfunction "P$2_P$2") (pintype "bidirectional"))
      (node (ref "C115") (pin "P$2") (pinfunction "P$2_P$2") (pintype "bidirectional"))
      (node (ref "C116") (pin "P$2") (pinfunction "P$2_P$2") (pintype "bidirectional"))
      (node (ref "C117") (pin "P$2") (pinfunction "P$2_P$2") (pintype "bidirectional"))
      (node (ref "C118") (pin "P$2") (pinfunction "P$2_P$2") (pintype "bidirectional"))
      (node (ref "C201") (pin "P$2") (pinfunction "P$2_P$2") (pintype "bidirectional"))
      (node (ref "C202") (pin "P$2") (pinfunction "P$2_P$2") (pintype "bidirectional"))
      (node (ref "C203") (pin "P$2") (pinfunction "P$2_P$2") (pintype "bidirectional"))
      (node (ref "C204") (pin "P$2") (pinfunction "P$2_P$2") (pintype "bidirectional"))
      (node (ref "C205") (pin "P$2") (pinfunction "P$2_P$2") (pintype "bidirectional"))
      (node (ref "C206") (pin "P$2") (pinfunction "P$2_P$2") (pintype "bidirectional"))
      (node (ref "C207") (pin "P$2") (pinfunction "P$2_P$2") (pintype "bidirectional"))
      (node (ref "C208") (pin "P$2") (pinfunction "P$2_P$2") (pintype "bidirectional"))
      (node (ref "C209") (pin "P$2") (pinfunction "P$2_P$2") (pintype "bidirectional"))
      (node (ref "C210") (pin "P$2") (pinfunction "P$2_P$2") (pintype "bidirectional"))
      (node (ref "C211") (pin "P$2") (pinfunction "P$2_P$2") (pintype "bidirectional"))
      (node (ref "C212") (pin "P$2") (pinfunction "P$2_P$2") (pintype "bidirectional"))
      (node (ref "C213") (pin "P$2") (pinfunction "P$2_P$2") (pintype "bidirectional"))
      (node (ref "C214") (pin "P$2") (pinfunction "P$2_P$2") (pintype "bidirectional"))
      (node (ref "C215") (pin "P$2") (pinfunction "P$2_P$2") (pintype "bidirectional"))
      (node (ref "C216") (pin "P$2") (pinfunction "P$2_P$2") (pintype "bidirectional"))
      (node (ref "C217") (pin "P$2") (pinfunction "P$2_P$2") (pintype "bidirectional"))
      (node (ref "C218") (pin "P$2") (pinfunction "P$2_P$2") (pintype "bidirectional"))
      (node (ref "C219") (pin "P$2") (pinfunction "P$2_P$2") (pintype "bidirectional"))
      (node (ref "C220") (pin "P$2") (pinfunction "P$2_P$2") (pintype "bidirectional"))
      (node (ref "C221") (pin "P$2") (pinfunction "P$2_P$2") (pintype "bidirectional"))
      (node (ref "C222") (pin "P$2") (pinfunction "P$2_P$2") (pintype "bidirectional"))
      (node (ref "C223") (pin "P$2") (pinfunction "P$2_P$2") (pintype "bidirectional"))
      (node (ref "C224") (pin "P$2") (pinfunction "P$2_P$2") (pintype "bidirectional"))
      (node (ref "C225") (pin "P$2") (pinfunction "P$2_P$2") (pintype "bidirectional"))
      (node (ref "C226") (pin "P$2") (pinfunction "P$2_P$2") (pintype "bidirectional"))
      (node (ref "C227") (pin "P$2") (pinfunction "P$2_P$2") (pintype "bidirectional"))
      (node (ref "C228") (pin "P$2") (pinfunction "P$2_P$2") (pintype "bidirectional"))
      (node (ref "C301") (pin "P$2") (pinfunction "P$2_P$2") (pintype "bidirectional"))
      (node (ref "C302") (pin "-") (pinfunction "CA_-") (pintype "bidirectional"))
      (node (ref "C303") (pin "-") (pinfunction "CA_-") (pintype "bidirectional"))
      (node (ref "C304") (pin "-") (pinfunction "CA_-") (pintype "bidirectional"))
      (node (ref "C305") (pin "P$2") (pinfunction "P$2_P$2") (pintype "bidirectional"))
      (node (ref "C306") (pin "-") (pinfunction "CA_-") (pintype "bidirectional"))
      (node (ref "C307") (pin "-") (pinfunction "CA_-") (pintype "bidirectional"))
      (node (ref "C308") (pin "-") (pinfunction "CA_-") (pintype "bidirectional"))
      (node (ref "C309") (pin "P$2") (pinfunction "P$2_P$2") (pintype "bidirectional"))
      (node (ref "C310") (pin "P$2") (pinfunction "P$2_P$2") (pintype "bidirectional"))
      (node (ref "C401") (pin "P$2") (pinfunction "P$2_P$2") (pintype "bidirectional"))
      (node (ref "C402") (pin "P$2") (pinfunction "P$2_P$2") (pintype "bidirectional"))
      (node (ref "C403") (pin "P$2") (pinfunction "P$2_P$2") (pintype "bidirectional"))
      (node (ref "C404") (pin "P$2") (pinfunction "P$2_P$2") (pintype "bidirectional"))
      (node (ref "C405") (pin "P$2") (pinfunction "P$2_P$2") (pintype "bidirectional"))
      (node (ref "C406") (pin "P$2") (pinfunction "P$2_P$2") (pintype "bidirectional"))
      (node (ref "C407") (pin "P$2") (pinfunction "P$2_P$2") (pintype "bidirectional"))
      (node (ref "C408") (pin "P$2") (pinfunction "P$2_P$2") (pintype "bidirectional"))
      (node (ref "C409") (pin "P$2") (pinfunction "P$2_P$2") (pintype "bidirectional"))
      (node (ref "C410") (pin "P$2") (pinfunction "P$2_P$2") (pintype "bidirectional"))
      (node (ref "C411") (pin "P$2") (pinfunction "P$2_P$2") (pintype "bidirectional"))
      (node (ref "C412") (pin "P$2") (pinfunction "P$2_P$2") (pintype "bidirectional"))
      (node (ref "C413") (pin "P$2") (pinfunction "P$2_P$2") (pintype "bidirectional"))
      (node (ref "C414") (pin "P$2") (pinfunction "P$2_P$2") (pintype "bidirectional"))
      (node (ref "C415") (pin "P$2") (pinfunction "P$2_P$2") (pintype "bidirectional"))
      (node (ref "C416") (pin "P$2") (pinfunction "P$2_P$2") (pintype "bidirectional"))
      (node (ref "C421") (pin "P$2") (pinfunction "P$2_P$2") (pintype "bidirectional"))
      (node (ref "C422") (pin "P$2") (pinfunction "P$2_P$2") (pintype "bidirectional"))
      (node (ref "C423") (pin "P$2") (pinfunction "P$2_P$2") (pintype "bidirectional"))
      (node (ref "C424") (pin "P$2") (pinfunction "P$2_P$2") (pintype "bidirectional"))
      (node (ref "C425") (pin "P$2") (pinfunction "P$2_P$2") (pintype "bidirectional"))
      (node (ref "C426") (pin "P$1") (pinfunction "P$1_P$1") (pintype "bidirectional"))
      (node (ref "C428") (pin "P$2") (pinfunction "P$2_P$2") (pintype "bidirectional"))
      (node (ref "C429") (pin "P$1") (pinfunction "P$1_P$1") (pintype "bidirectional"))
      (node (ref "C431") (pin "P$2") (pinfunction "P$2_P$2") (pintype "bidirectional"))
      (node (ref "C432") (pin "P$2") (pinfunction "P$2_P$2") (pintype "bidirectional"))
      (node (ref "C501") (pin "P$2") (pinfunction "P$2_P$2") (pintype "bidirectional"))
      (node (ref "C502") (pin "P$2") (pinfunction "P$2_P$2") (pintype "bidirectional"))
      (node (ref "C503") (pin "P$2") (pinfunction "P$2_P$2") (pintype "bidirectional"))
      (node (ref "D101") (pin "P$1") (pinfunction "1_P$1") (pintype "bidirectional"))
      (node (ref "D201") (pin "P$1") (pinfunction "1_P$1") (pintype "bidirectional"))
      (node (ref "D202") (pin "P$1") (pinfunction "1_P$1") (pintype "bidirectional"))
      (node (ref "D203") (pin "P$1") (pinfunction "1_P$1") (pintype "bidirectional"))
      (node (ref "D301") (pin "A") (pinfunction "A_A") (pintype "bidirectional"))
      (node (ref "D302") (pin "C") (pinfunction "CA_C") (pintype "bidirectional"))
      (node (ref "D503") (pin "1") (pinfunction "1_1") (pintype "bidirectional"))
      (node (ref "D504") (pin "P$1") (pinfunction "1_P$1") (pintype "bidirectional"))
      (node (ref "D505") (pin "P$1") (pinfunction "1_P$1") (pintype "bidirectional"))
      (node (ref "D506") (pin "P$1") (pinfunction "1_P$1") (pintype "bidirectional"))
      (node (ref "J201") (pin "5") (pinfunction "S_5") (pintype "passive"))
      (node (ref "J201") (pin "FIT@1") (pinfunction "S_FIT@1") (pintype "passive"))
      (node (ref "J201") (pin "FIT@2") (pinfunction "S_FIT@2") (pintype "passive"))
      (node (ref "J202") (pin "5") (pinfunction "S_5") (pintype "passive"))
      (node (ref "J202") (pin "FIT@1") (pinfunction "S_FIT@1") (pintype "passive"))
      (node (ref "J202") (pin "FIT@2") (pinfunction "S_FIT@2") (pintype "passive"))
      (node (ref "J203") (pin "5") (pinfunction "S_5") (pintype "passive"))
      (node (ref "J203") (pin "FIT@1") (pinfunction "S_FIT@1") (pintype "passive"))
      (node (ref "J203") (pin "FIT@2") (pinfunction "S_FIT@2") (pintype "passive"))
      (node (ref "J204") (pin "5") (pinfunction "S_5") (pintype "passive"))
      (node (ref "J204") (pin "FIT@1") (pinfunction "S_FIT@1") (pintype "passive"))
      (node (ref "J204") (pin "FIT@2") (pinfunction "S_FIT@2") (pintype "passive"))
      (node (ref "J205") (pin "5") (pinfunction "S_5") (pintype "passive"))
      (node (ref "J205") (pin "FIT@1") (pinfunction "S_FIT@1") (pintype "passive"))
      (node (ref "J205") (pin "FIT@2") (pinfunction "S_FIT@2") (pintype "passive"))
      (node (ref "J301") (pin "1") (pinfunction "S_1") (pintype "passive"))
      (node (ref "J302") (pin "2") (pinfunction "S_2") (pintype "passive"))
      (node (ref "J402") (pin "FIT@1") (pinfunction "S_FIT@1") (pintype "passive"))
      (node (ref "J402") (pin "FIT@2") (pinfunction "S_FIT@2") (pintype "passive"))
      (node (ref "J501") (pin "6") (pinfunction "S_6") (pintype "passive"))
      (node (ref "J501") (pin "FIT@1") (pinfunction "S_FIT@1") (pintype "passive"))
      (node (ref "J501") (pin "FIT@2") (pinfunction "S_FIT@2") (pintype "passive"))
      (node (ref "J502") (pin "3") (pinfunction "S_3") (pintype "passive"))
      (node (ref "J502") (pin "FIT@1") (pinfunction "S_FIT@1") (pintype "passive"))
      (node (ref "J502") (pin "FIT@2") (pinfunction "S_FIT@2") (pintype "passive"))
      (node (ref "J503") (pin "GND") (pinfunction "GND_GND") (pintype "bidirectional"))
      (node (ref "J503") (pin "GND@1") (pinfunction "CASE_GND@1") (pintype "bidirectional"))
      (node (ref "J503") (pin "GND@2") (pinfunction "CASE_GND@2") (pintype "bidirectional"))
      (node (ref "J503") (pin "GND@3") (pinfunction "CASE_GND@3") (pintype "bidirectional"))
      (node (ref "J503") (pin "GND@4") (pinfunction "CASE_GND@4") (pintype "bidirectional"))
      (node (ref "J504") (pin "2") (pinfunction "S_2") (pintype "passive"))
      (node (ref "J504") (pin "FIT@1") (pinfunction "S_FIT@1") (pintype "passive"))
      (node (ref "J504") (pin "FIT@2") (pinfunction "S_FIT@2") (pintype "passive"))
      (node (ref "J505") (pin "10") (pinfunction "S_10") (pintype "passive"))
      (node (ref "J505") (pin "6") (pinfunction "S_6") (pintype "passive"))
      (node (ref "J505") (pin "8") (pinfunction "S_8") (pintype "passive"))
      (node (ref "J505") (pin "TAB1") (pinfunction "S_TAB1") (pintype "passive"))
      (node (ref "J505") (pin "TAB2") (pinfunction "S_TAB2") (pintype "passive"))
      (node (ref "J506") (pin "3") (pinfunction "S_3") (pintype "passive"))
      (node (ref "J506") (pin "FIT@1") (pinfunction "S_FIT@1") (pintype "passive"))
      (node (ref "J506") (pin "FIT@2") (pinfunction "S_FIT@2") (pintype "passive"))
      (node (ref "P302") (pin "H1") (pinfunction "S_H1") (pintype "passive"))
      (node (ref "P302") (pin "H10") (pinfunction "S_H10") (pintype "passive"))
      (node (ref "P302") (pin "H11") (pinfunction "S_H11") (pintype "passive"))
      (node (ref "P302") (pin "H12") (pinfunction "S_H12") (pintype "passive"))
      (node (ref "P302") (pin "H2") (pinfunction "S_H2") (pintype "passive"))
      (node (ref "P302") (pin "H3") (pinfunction "S_H3") (pintype "passive"))
      (node (ref "P302") (pin "H4") (pinfunction "S_H4") (pintype "passive"))
      (node (ref "P302") (pin "H5") (pinfunction "S_H5") (pintype "passive"))
      (node (ref "P302") (pin "H6") (pinfunction "S_H6") (pintype "passive"))
      (node (ref "P302") (pin "H7") (pinfunction "S_H7") (pintype "passive"))
      (node (ref "P302") (pin "H8") (pinfunction "S_H8") (pintype "passive"))
      (node (ref "P302") (pin "H9") (pinfunction "S_H9") (pintype "passive"))
      (node (ref "P302") (pin "PAD") (pinfunction "S_PAD") (pintype "passive"))
      (node (ref "Q405") (pin "S1") (pinfunction "S1_S1") (pintype "bidirectional"))
      (node (ref "Q405") (pin "S2") (pinfunction "S1_S2") (pintype "bidirectional"))
      (node (ref "Q405") (pin "S3") (pinfunction "S1_S3") (pintype "bidirectional"))
      (node (ref "Q405") (pin "S4") (pinfunction "S1_S4") (pintype "bidirectional"))
      (node (ref "Q405") (pin "S5") (pinfunction "S1_S5") (pintype "bidirectional"))
      (node (ref "Q406") (pin "S1") (pinfunction "S1_S1") (pintype "bidirectional"))
      (node (ref "Q406") (pin "S2") (pinfunction "S1_S2") (pintype "bidirectional"))
      (node (ref "Q406") (pin "S3") (pinfunction "S1_S3") (pintype "bidirectional"))
      (node (ref "Q406") (pin "S4") (pinfunction "S1_S4") (pintype "bidirectional"))
      (node (ref "Q406") (pin "S5") (pinfunction "S1_S5") (pintype "bidirectional"))
      (node (ref "Q407") (pin "S1") (pinfunction "S1_S1") (pintype "bidirectional"))
      (node (ref "Q407") (pin "S2") (pinfunction "S1_S2") (pintype "bidirectional"))
      (node (ref "Q407") (pin "S3") (pinfunction "S1_S3") (pintype "bidirectional"))
      (node (ref "Q407") (pin "S4") (pinfunction "S1_S4") (pintype "bidirectional"))
      (node (ref "Q407") (pin "S5") (pinfunction "S1_S5") (pintype "bidirectional"))
      (node (ref "Q408") (pin "S1") (pinfunction "S1_S1") (pintype "bidirectional"))
      (node (ref "Q408") (pin "S2") (pinfunction "S1_S2") (pintype "bidirectional"))
      (node (ref "Q408") (pin "S3") (pinfunction "S1_S3") (pintype "bidirectional"))
      (node (ref "Q408") (pin "S4") (pinfunction "S1_S4") (pintype "bidirectional"))
      (node (ref "Q408") (pin "S5") (pinfunction "S1_S5") (pintype "bidirectional"))
      (node (ref "Q409") (pin "S1") (pinfunction "S1_S1") (pintype "bidirectional"))
      (node (ref "Q409") (pin "S2") (pinfunction "S1_S2") (pintype "bidirectional"))
      (node (ref "Q409") (pin "S3") (pinfunction "S1_S3") (pintype "bidirectional"))
      (node (ref "Q409") (pin "S4") (pinfunction "S1_S4") (pintype "bidirectional"))
      (node (ref "Q409") (pin "S5") (pinfunction "S1_S5") (pintype "bidirectional"))
      (node (ref "R104") (pin "P$1") (pinfunction "P$1_P$1") (pintype "bidirectional"))
      (node (ref "R105") (pin "P$1") (pinfunction "P$1_P$1") (pintype "bidirectional"))
      (node (ref "R107") (pin "P$1") (pinfunction "P$1_P$1") (pintype "bidirectional"))
      (node (ref "R108") (pin "P$1") (pinfunction "P$1_P$1") (pintype "bidirectional"))
      (node (ref "R110") (pin "P$1") (pinfunction "P$1_P$1") (pintype "bidirectional"))
      (node (ref "R114") (pin "P$2") (pinfunction "P$2_P$2") (pintype "bidirectional"))
      (node (ref "R116") (pin "P$1") (pinfunction "P$1_P$1") (pintype "bidirectional"))
      (node (ref "R118") (pin "P$1") (pinfunction "P$1_P$1") (pintype "bidirectional"))
      (node (ref "R121") (pin "P$1") (pinfunction "P$1_P$1") (pintype "bidirectional"))
      (node (ref "R302") (pin "P$1") (pinfunction "P$1_P$1") (pintype "bidirectional"))
      (node (ref "R304") (pin "P$1") (pinfunction "P$1_P$1") (pintype "bidirectional"))
      (node (ref "R401") (pin "P$1") (pinfunction "P$1_P$1") (pintype "bidirectional"))
      (node (ref "R402") (pin "P$1") (pinfunction "P$1_P$1") (pintype "bidirectional"))
      (node (ref "R403") (pin "P$1") (pinfunction "P$1_P$1") (pintype "bidirectional"))
      (node (ref "R404") (pin "P$1") (pinfunction "P$1_P$1") (pintype "bidirectional"))
      (node (ref "R405") (pin "P$1") (pinfunction "P$1_P$1") (pintype "bidirectional"))
      (node (ref "R406") (pin "P$1") (pinfunction "P$1_P$1") (pintype "bidirectional"))
      (node (ref "R407") (pin "P$1") (pinfunction "P$1_P$1") (pintype "bidirectional"))
      (node (ref "R408") (pin "P$1") (pinfunction "P$1_P$1") (pintype "bidirectional"))
      (node (ref "R428") (pin "P$1") (pinfunction "P$1_P$1") (pintype "bidirectional"))
      (node (ref "R430") (pin "P$1") (pinfunction "P$1_P$1") (pintype "bidirectional"))
      (node (ref "R505") (pin "P$1") (pinfunction "P$1_P$1") (pintype "bidirectional"))
      (node (ref "R507") (pin "P$2") (pinfunction "P$2_P$2") (pintype "bidirectional"))
      (node (ref "R510") (pin "P$1") (pinfunction "P$1_P$1") (pintype "bidirectional"))
      (node (ref "R511") (pin "P$1") (pinfunction "P$1_P$1") (pintype "bidirectional"))
      (node (ref "U101") (pin "3") (pinfunction "GND_3") (pintype "bidirectional"))
      (node (ref "U102") (pin "14") (pinfunction "GND_14") (pintype "bidirectional"))
      (node (ref "U102") (pin "24") (pinfunction "GNDA_24") (pintype "bidirectional"))
      (node (ref "U102") (pin "3") (pinfunction "GND_3") (pintype "bidirectional"))
      (node (ref "U102") (pin "44") (pinfunction "GND_44") (pintype "bidirectional"))
      (node (ref "U102") (pin "53") (pinfunction "PLL_GND_53") (pintype "bidirectional"))
      (node (ref "U102") (pin "54") (pinfunction "TEST_54") (pintype "bidirectional"))
      (node (ref "U102") (pin "62") (pinfunction "GND_62") (pintype "bidirectional"))
      (node (ref "U102") (pin "73") (pinfunction "GND_73") (pintype "bidirectional"))
      (node (ref "U102") (pin "PAD") (pinfunction "GNDP_PAD") (pintype "bidirectional"))
      (node (ref "U201") (pin "2") (pinfunction "GND_2") (pintype "bidirectional"))
      (node (ref "U202") (pin "2") (pinfunction "GND_2") (pintype "bidirectional"))
      (node (ref "U203") (pin "2") (pinfunction "GND_2") (pintype "bidirectional"))
      (node (ref "U204") (pin "2") (pinfunction "GND_2") (pintype "bidirectional"))
      (node (ref "U205") (pin "4") (pinfunction "GND_4") (pintype "bidirectional"))
      (node (ref "U206") (pin "4") (pinfunction "GND_4") (pintype "bidirectional"))
      (node (ref "U207") (pin "4") (pinfunction "GND_4") (pintype "bidirectional"))
      (node (ref "U208") (pin "4") (pinfunction "GND_4") (pintype "bidirectional"))
      (node (ref "U301") (pin "2") (pinfunction "GND_2") (pintype "bidirectional"))
      (node (ref "U301") (pin "4") (pinfunction "SHDN_4") (pintype "bidirectional"))
      (node (ref "U301") (pin "6") (pinfunction "GND_6") (pintype "bidirectional"))
      (node (ref "U301") (pin "7") (pinfunction "GND_7") (pintype "bidirectional"))
      (node (ref "U302") (pin "5") (pinfunction "GND_5") (pintype "bidirectional"))
      (node (ref "U302") (pin "6") (pinfunction "GND_6") (pintype "bidirectional"))
      (node (ref "U302") (pin "7") (pinfunction "GND_7") (pintype "bidirectional"))
      (node (ref "U302") (pin "8") (pinfunction "GND_8") (pintype "bidirectional"))
      (node (ref "U303") (pin "5") (pinfunction "GND_5") (pintype "bidirectional"))
      (node (ref "U303") (pin "6") (pinfunction "GND_6") (pintype "bidirectional"))
      (node (ref "U303") (pin "7") (pinfunction "GND_7") (pintype "bidirectional"))
      (node (ref "U303") (pin "8") (pinfunction "GND_8") (pintype "bidirectional"))
      (node (ref "U401") (pin "4") (pinfunction "GNDI_4") (pintype "bidirectional"))
      (node (ref "U401") (pin "9") (pinfunction "GNB_9") (pintype "bidirectional"))
      (node (ref "U402") (pin "4") (pinfunction "GNDI_4") (pintype "bidirectional"))
      (node (ref "U402") (pin "9") (pinfunction "GNB_9") (pintype "bidirectional"))
      (node (ref "U403") (pin "4") (pinfunction "GNDI_4") (pintype "bidirectional"))
      (node (ref "U403") (pin "9") (pinfunction "GNB_9") (pintype "bidirectional"))
      (node (ref "U404") (pin "4") (pinfunction "GNDI_4") (pintype "bidirectional"))
      (node (ref "U404") (pin "9") (pinfunction "GNB_9") (pintype "bidirectional"))
      (node (ref "U405") (pin "2") (pinfunction "P$1_2") (pintype "bidirectional"))
      (node (ref "U405") (pin "3") (pinfunction "P$1_3") (pintype "bidirectional"))
      (node (ref "U406") (pin "2") (pinfunction "P$1_2") (pintype "bidirectional"))
      (node (ref "U406") (pin "3") (pinfunction "P$1_3") (pintype "bidirectional"))
      (node (ref "U407") (pin "3") (pinfunction "CA_3") (pintype "bidirectional"))
      (node (ref "U407") (pin "5") (pinfunction "GNB_5") (pintype "bidirectional"))
      (node (ref "U501") (pin "2") (pinfunction "GND_2") (pintype "bidirectional"))
      (node (ref "U501") (pin "PAD") (pinfunction "GNDP_PAD") (pintype "bidirectional"))
    )
    (net (code "32") (name "HALL_UX") (class "Default")
      (node (ref "U102") (pin "38") (pinfunction "HALL_UX_38") (pintype "bidirectional"))
      (node (ref "U207") (pin "2") (pinfunction "Y_2") (pintype "output"))
    )
    (net (code "33") (name "HALL_V") (class "Default")
      (node (ref "U102") (pin "37") (pinfunction "HALL_V_37") (pintype "bidirectional"))
      (node (ref "U207") (pin "5") (pinfunction "Y_5") (pintype "output"))
    )
    (net (code "34") (name "HALL_WY") (class "Default")
      (node (ref "U102") (pin "36") (pinfunction "HALL_WY_36") (pintype "bidirectional"))
      (node (ref "U207") (pin "7") (pinfunction "Y_7") (pintype "output"))
    )
    (net (code "35") (name "INT") (class "Default")
      (node (ref "J501") (pin "5") (pinfunction "S_5") (pintype "passive"))
      (node (ref "JP507") (pin "2") (pinfunction "2_2") (pintype "passive"))
      (node (ref "U102") (pin "12") (pinfunction "STATUS_12") (pintype "bidirectional"))
    )
    (net (code "36") (name "MISO") (class "Default")
      (node (ref "J501") (pin "4") (pinfunction "S_4") (pintype "passive"))
      (node (ref "JP501") (pin "2") (pinfunction "2_2") (pintype "passive"))
      (node (ref "U102") (pin "9") (pinfunction "SPI_MISO_9") (pintype "bidirectional"))
    )
    (net (code "37") (name "MOSI") (class "Default")
      (node (ref "J501") (pin "3") (pinfunction "S_3") (pintype "passive"))
      (node (ref "JP502") (pin "2") (pinfunction "2_2") (pintype "passive"))
      (node (ref "U102") (pin "8") (pinfunction "SPI_MOSI_8") (pintype "bidirectional"))
    )
    (net (code "38") (name "Net-(C307-AN)") (class "Default")
      (node (ref "C305") (pin "P$1") (pinfunction "P$1_P$1") (pintype "bidirectional"))
      (node (ref "C307") (pin "+") (pinfunction "AN_+") (pintype "bidirectional"))
      (node (ref "L301") (pin "2") (pinfunction "P$2_2") (pintype "bidirectional"))
      (node (ref "R303") (pin "P$2") (pinfunction "P$2_P$2") (pintype "bidirectional"))
      (node (ref "R305") (pin "P$2") (pinfunction "P$2_P$2") (pintype "bidirectional"))
      (node (ref "U302") (pin "1") (pinfunction "EN_1") (pintype "bidirectional"))
      (node (ref "U302") (pin "2") (pinfunction "VIN_2") (pintype "bidirectional"))
      (node (ref "U303") (pin "1") (pinfunction "EN_1") (pintype "bidirectional"))
      (node (ref "U303") (pin "2") (pinfunction "VIN_2") (pintype "bidirectional"))
    )
    (net (code "39") (name "Net-(D101-3)") (class "Default")
      (node (ref "C118") (pin "P$1") (pinfunction "P$1_P$1") (pintype "bidirectional"))
      (node (ref "D101") (pin "P$3") (pinfunction "3_P$3") (pintype "bidirectional"))
      (node (ref "R116") (pin "P$2") (pinfunction "P$2_P$2") (pintype "bidirectional"))
      (node (ref "R119") (pin "P$1") (pinfunction "P$1_P$1") (pintype "bidirectional"))
      (node (ref "U102") (pin "20") (pinfunction "ADC_VM_20") (pintype "bidirectional"))
    )
    (net (code "40") (name "Net-(D302-AN)") (class "Default")
      (node (ref "D302") (pin "A") (pinfunction "AN_A") (pintype "bidirectional"))
      (node (ref "R305") (pin "P$1") (pinfunction "P$1_P$1") (pintype "bidirectional"))
      (node (ref "U302") (pin "4") (pinfunction "FLG_4") (pintype "bidirectional"))
      (node (ref "U303") (pin "4") (pinfunction "FLG_4") (pintype "bidirectional"))
    )
    (net (code "41") (name "Net-(D401-PadA)") (class "Default")
      (node (ref "D401") (pin "A") (pinfunction "A_A") (pintype "passive"))
      (node (ref "R409") (pin "P$2") (pinfunction "P$2_P$2") (pintype "bidirectional"))
    )
    (net (code "42") (name "Net-(D402-PadA)") (class "Default")
      (node (ref "D402") (pin "A") (pinfunction "A_A") (pintype "passive"))
      (node (ref "R410") (pin "P$2") (pinfunction "P$2_P$2") (pintype "bidirectional"))
    )
    (net (code "43") (name "Net-(D403-PadA)") (class "Default")
      (node (ref "D403") (pin "A") (pinfunction "A_A") (pintype "passive"))
      (node (ref "R411") (pin "P$2") (pinfunction "P$2_P$2") (pintype "bidirectional"))
    )
    (net (code "44") (name "Net-(D404-PadA)") (class "Default")
      (node (ref "D404") (pin "A") (pinfunction "A_A") (pintype "passive"))
      (node (ref "R412") (pin "P$2") (pinfunction "P$2_P$2") (pintype "bidirectional"))
    )
    (net (code "45") (name "Net-(D501-AN)") (class "Default")
      (node (ref "D501") (pin "A") (pinfunction "AN_A") (pintype "bidirectional"))
      (node (ref "R502") (pin "P$1") (pinfunction "P$1_P$1") (pintype "bidirectional"))
    )
    (net (code "46") (name "Net-(D501-CA)") (class "Default")
      (node (ref "D501") (pin "C") (pinfunction "CA_C") (pintype "bidirectional"))
      (node (ref "U501") (pin "14") (pinfunction "(GPIO0-TXT)GPIO7-~{CS7}_14") (pintype "bidirectional"))
    )
    (net (code "47") (name "Net-(D502-AN)") (class "Default")
      (node (ref "D502") (pin "A") (pinfunction "AN_A") (pintype "bidirectional"))
      (node (ref "R503") (pin "P$1") (pinfunction "P$1_P$1") (pintype "bidirectional"))
    )
    (net (code "48") (name "Net-(D502-CA)") (class "Default")
      (node (ref "D502") (pin "C") (pinfunction "CA_C") (pintype "bidirectional"))
      (node (ref "U501") (pin "13") (pinfunction "(GPIO1-RXT)GPIO8-~{CS8}-SPIACT_13") (pintype "bidirectional"))
    )
    (net (code "49") (name "Net-(D503-Pad4)") (class "Default")
      (node (ref "D503") (pin "4") (pinfunction "4_4") (pintype "bidirectional"))
      (node (ref "J503") (pin "VBUS") (pinfunction "VBUS_VBUS") (pintype "bidirectional"))
      (node (ref "R506") (pin "P$1") (pinfunction "P$1_P$1") (pintype "bidirectional"))
    )
    (net (code "50") (name "Net-(J201B-S)") (class "Default")
      (node (ref "J201") (pin "2") (pinfunction "S_2") (pintype "passive"))
      (node (ref "R201") (pin "P$1") (pinfunction "P$1_P$1") (pintype "bidirectional"))
    )
    (net (code "51") (name "Net-(J201C-S)") (class "Default")
      (node (ref "J201") (pin "3") (pinfunction "S_3") (pintype "passive"))
      (node (ref "R202") (pin "P$1") (pinfunction "P$1_P$1") (pintype "bidirectional"))
    )
    (net (code "52") (name "Net-(J201D-S)") (class "Default")
      (node (ref "J201") (pin "4") (pinfunction "S_4") (pintype "passive"))
      (node (ref "R203") (pin "P$1") (pinfunction "P$1_P$1") (pintype "bidirectional"))
    )
    (net (code "53") (name "Net-(J202B-S)") (class "Default")
      (node (ref "J202") (pin "2") (pinfunction "S_2") (pintype "passive"))
      (node (ref "R204") (pin "P$1") (pinfunction "P$1_P$1") (pintype "bidirectional"))
    )
    (net (code "54") (name "Net-(J202C-S)") (class "Default")
      (node (ref "J202") (pin "3") (pinfunction "S_3") (pintype "passive"))
      (node (ref "R205") (pin "P$1") (pinfunction "P$1_P$1") (pintype "bidirectional"))
    )
    (net (code "55") (name "Net-(J202D-S)") (class "Default")
      (node (ref "J202") (pin "4") (pinfunction "S_4") (pintype "passive"))
      (node (ref "R206") (pin "P$1") (pinfunction "P$1_P$1") (pintype "bidirectional"))
    )
    (net (code "56") (name "Net-(J203B-S)") (class "Default")
      (node (ref "J203") (pin "2") (pinfunction "S_2") (pintype "passive"))
      (node (ref "R207") (pin "P$1") (pinfunction "P$1_P$1") (pintype "bidirectional"))
    )
    (net (code "57") (name "Net-(J203C-S)") (class "Default")
      (node (ref "J203") (pin "3") (pinfunction "S_3") (pintype "passive"))
      (node (ref "R208") (pin "P$1") (pinfunction "P$1_P$1") (pintype "bidirectional"))
    )
    (net (code "58") (name "Net-(J203D-S)") (class "Default")
      (node (ref "J203") (pin "4") (pinfunction "S_4") (pintype "passive"))
      (node (ref "R209") (pin "P$1") (pinfunction "P$1_P$1") (pintype "bidirectional"))
    )
    (net (code "59") (name "Net-(J204B-S)") (class "Default")
      (node (ref "J204") (pin "2") (pinfunction "S_2") (pintype "passive"))
      (node (ref "R210") (pin "P$1") (pinfunction "P$1_P$1") (pintype "bidirectional"))
    )
    (net (code "60") (name "Net-(J204C-S)") (class "Default")
      (node (ref "J204") (pin "3") (pinfunction "S_3") (pintype "passive"))
      (node (ref "R211") (pin "P$1") (pinfunction "P$1_P$1") (pintype "bidirectional"))
    )
    (net (code "61") (name "Net-(J204D-S)") (class "Default")
      (node (ref "J204") (pin "4") (pinfunction "S_4") (pintype "passive"))
      (node (ref "R212") (pin "P$1") (pinfunction "P$1_P$1") (pintype "bidirectional"))
    )
    (net (code "62") (name "Net-(J205B-S)") (class "Default")
      (node (ref "J205") (pin "2") (pinfunction "S_2") (pintype "passive"))
      (node (ref "R213") (pin "P$1") (pinfunction "P$1_P$1") (pintype "bidirectional"))
    )
    (net (code "63") (name "Net-(J205C-S)") (class "Default")
      (node (ref "J205") (pin "3") (pinfunction "S_3") (pintype "passive"))
      (node (ref "R218") (pin "P$1") (pinfunction "P$1_P$1") (pintype "bidirectional"))
    )
    (net (code "64") (name "Net-(J205D-S)") (class "Default")
      (node (ref "J205") (pin "4") (pinfunction "S_4") (pintype "passive"))
      (node (ref "R227") (pin "P$1") (pinfunction "P$1_P$1") (pintype "bidirectional"))
    )
    (net (code "65") (name "Net-(J401A-S)") (class "Default")
      (node (ref "J401") (pin "1") (pinfunction "S_1") (pintype "passive"))
      (node (ref "P403") (pin "H1") (pinfunction "S_H1") (pintype "passive"))
      (node (ref "P403") (pin "H10") (pinfunction "S_H10") (pintype "passive"))
      (node (ref "P403") (pin "H11") (pinfunction "S_H11") (pintype "passive"))
      (node (ref "P403") (pin "H12") (pinfunction "S_H12") (pintype "passive"))
      (node (ref "P403") (pin "H2") (pinfunction "S_H2") (pintype "passive"))
      (node (ref "P403") (pin "H3") (pinfunction "S_H3") (pintype "passive"))
      (node (ref "P403") (pin "H4") (pinfunction "S_H4") (pintype "passive"))
      (node (ref "P403") (pin "H5") (pinfunction "S_H5") (pintype "passive"))
      (node (ref "P403") (pin "H6") (pinfunction "S_H6") (pintype "passive"))
      (node (ref "P403") (pin "H7") (pinfunction "S_H7") (pintype "passive"))
      (node (ref "P403") (pin "H8") (pinfunction "S_H8") (pintype "passive"))
      (node (ref "P403") (pin "H9") (pinfunction "S_H9") (pintype "passive"))
      (node (ref "P403") (pin "PAD") (pinfunction "S_PAD") (pintype "passive"))
      (node (ref "R421") (pin "3") (pinfunction "P$2_3") (pintype "bidirectional"))
      (node (ref "R421") (pin "4") (pinfunction "P$2_4") (pintype "bidirectional"))
    )
    (net (code "66") (name "Net-(J401C-S)") (class "Default")
      (node (ref "J401") (pin "3") (pinfunction "S_3") (pintype "passive"))
      (node (ref "P404") (pin "H1") (pinfunction "S_H1") (pintype "passive"))
      (node (ref "P404") (pin "H10") (pinfunction "S_H10") (pintype "passive"))
      (node (ref "P404") (pin "H11") (pinfunction "S_H11") (pintype "passive"))
      (node (ref "P404") (pin "H12") (pinfunction "S_H12") (pintype "passive"))
      (node (ref "P404") (pin "H2") (pinfunction "S_H2") (pintype "passive"))
      (node (ref "P404") (pin "H3") (pinfunction "S_H3") (pintype "passive"))
      (node (ref "P404") (pin "H4") (pinfunction "S_H4") (pintype "passive"))
      (node (ref "P404") (pin "H5") (pinfunction "S_H5") (pintype "passive"))
      (node (ref "P404") (pin "H6") (pinfunction "S_H6") (pintype "passive"))
      (node (ref "P404") (pin "H7") (pinfunction "S_H7") (pintype "passive"))
      (node (ref "P404") (pin "H8") (pinfunction "S_H8") (pintype "passive"))
      (node (ref "P404") (pin "H9") (pinfunction "S_H9") (pintype "passive"))
      (node (ref "P404") (pin "PAD") (pinfunction "S_PAD") (pintype "passive"))
      (node (ref "R422") (pin "3") (pinfunction "P$2_3") (pintype "bidirectional"))
      (node (ref "R422") (pin "4") (pinfunction "P$2_4") (pintype "bidirectional"))
    )
    (net (code "67") (name "Net-(J403B-S)") (class "Default")
      (node (ref "J403") (pin "2") (pinfunction "S_2") (pintype "passive"))
      (node (ref "P406") (pin "H1") (pinfunction "S_H1") (pintype "passive"))
      (node (ref "P406") (pin "H10") (pinfunction "S_H10") (pintype "passive"))
      (node (ref "P406") (pin "H11") (pinfunction "S_H11") (pintype "passive"))
      (node (ref "P406") (pin "H12") (pinfunction "S_H12") (pintype "passive"))
      (node (ref "P406") (pin "H2") (pinfunction "S_H2") (pintype "passive"))
      (node (ref "P406") (pin "H3") (pinfunction "S_H3") (pintype "passive"))
      (node (ref "P406") (pin "H4") (pinfunction "S_H4") (pintype "passive"))
      (node (ref "P406") (pin "H5") (pinfunction "S_H5") (pintype "passive"))
      (node (ref "P406") (pin "H6") (pinfunction "S_H6") (pintype "passive"))
      (node (ref "P406") (pin "H7") (pinfunction "S_H7") (pintype "passive"))
      (node (ref "P406") (pin "H8") (pinfunction "S_H8") (pintype "passive"))
      (node (ref "P406") (pin "H9") (pinfunction "S_H9") (pintype "passive"))
      (node (ref "P406") (pin "PAD") (pinfunction "S_PAD") (pintype "passive"))
      (node (ref "Q409") (pin "D1") (pinfunction "D1_D1") (pintype "bidirectional"))
      (node (ref "Q409") (pin "D2") (pinfunction "D1_D2") (pintype "bidirectional"))
      (node (ref "Q409") (pin "D3") (pinfunction "D1_D3") (pintype "bidirectional"))
      (node (ref "Q409") (pin "D4") (pinfunction "D1_D4") (pintype "bidirectional"))
    )
    (net (code "68") (name "Net-(J504A-S)") (class "Default")
      (node (ref "J504") (pin "1") (pinfunction "S_1") (pintype "passive"))
      (node (ref "R504") (pin "P$1") (pinfunction "P$1_P$1") (pintype "bidirectional"))
    )
    (net (code "69") (name "Net-(J506A-S)") (class "Default")
      (node (ref "J506") (pin "1") (pinfunction "S_1") (pintype "passive"))
      (node (ref "R508") (pin "P$1") (pinfunction "P$1_P$1") (pintype "bidirectional"))
    )
    (net (code "70") (name "Net-(J506B-S)") (class "Default")
      (node (ref "J506") (pin "2") (pinfunction "S_2") (pintype "passive"))
      (node (ref "R509") (pin "P$1") (pinfunction "P$1_P$1") (pintype "bidirectional"))
    )
    (net (code "71") (name "Net-(L301-P$1)") (class "Default")
      (node (ref "D301") (pin "C") (pinfunction "C_C") (pintype "bidirectional"))
      (node (ref "L301") (pin "1") (pinfunction "P$1_1") (pintype "bidirectional"))
      (node (ref "U301") (pin "8") (pinfunction "SW_8") (pintype "bidirectional"))
    )
    (net (code "72") (name "Net-(Q401-G1)") (class "Default")
      (node (ref "Q401") (pin "G") (pinfunction "G1_G") (pintype "bidirectional"))
      (node (ref "R413") (pin "P$2") (pinfunction "P$2_P$2") (pintype "bidirectional"))
    )
    (net (code "73") (name "Net-(Q402-G1)") (class "Default")
      (node (ref "Q402") (pin "G") (pinfunction "G1_G") (pintype "bidirectional"))
      (node (ref "R414") (pin "P$2") (pinfunction "P$2_P$2") (pintype "bidirectional"))
    )
    (net (code "74") (name "Net-(Q403-G1)") (class "Default")
      (node (ref "Q403") (pin "G") (pinfunction "G1_G") (pintype "bidirectional"))
      (node (ref "R415") (pin "P$2") (pinfunction "P$2_P$2") (pintype "bidirectional"))
    )
    (net (code "75") (name "Net-(Q404-G1)") (class "Default")
      (node (ref "Q404") (pin "G") (pinfunction "G1_G") (pintype "bidirectional"))
      (node (ref "R416") (pin "P$2") (pinfunction "P$2_P$2") (pintype "bidirectional"))
    )
    (net (code "76") (name "Net-(Q405-G1)") (class "Default")
      (node (ref "Q405") (pin "G") (pinfunction "G1_G") (pintype "bidirectional"))
      (node (ref "R417") (pin "P$2") (pinfunction "P$2_P$2") (pintype "bidirectional"))
    )
    (net (code "77") (name "Net-(Q406-G1)") (class "Default")
      (node (ref "Q406") (pin "G") (pinfunction "G1_G") (pintype "bidirectional"))
      (node (ref "R418") (pin "P$2") (pinfunction "P$2_P$2") (pintype "bidirectional"))
    )
    (net (code "78") (name "Net-(Q407-G1)") (class "Default")
      (node (ref "Q407") (pin "G") (pinfunction "G1_G") (pintype "bidirectional"))
      (node (ref "R419") (pin "P$2") (pinfunction "P$2_P$2") (pintype "bidirectional"))
    )
    (net (code "79") (name "Net-(Q408-G1)") (class "Default")
      (node (ref "Q408") (pin "G") (pinfunction "G1_G") (pintype "bidirectional"))
      (node (ref "R420") (pin "P$2") (pinfunction "P$2_P$2") (pintype "bidirectional"))
    )
    (net (code "80") (name "Net-(Q409-G1)") (class "Default")
      (node (ref "Q409") (pin "G") (pinfunction "G1_G") (pintype "bidirectional"))
      (node (ref "R431") (pin "P$2") (pinfunction "P$2_P$2") (pintype "bidirectional"))
    )
    (net (code "81") (name "Net-(R421-PadSENSE+)") (class "Default")
      (node (ref "R421") (pin "SENSE+") (pinfunction "SENSE+_SENSE+") (pintype "bidirectional"))
      (node (ref "R424") (pin "P$1") (pinfunction "P$1_P$1") (pintype "bidirectional"))
    )
    (net (code "82") (name "Net-(R421-PadSENSE-)") (class "Default")
      (node (ref "R421") (pin "SENSE-") (pinfunction "SENSE-_SENSE-") (pintype "bidirectional"))
      (node (ref "R423") (pin "P$1") (pinfunction "P$1_P$1") (pintype "bidirectional"))
    )
    (net (code "83") (name "Net-(R422-PadSENSE+)") (class "Default")
      (node (ref "R422") (pin "SENSE+") (pinfunction "SENSE+_SENSE+") (pintype "bidirectional"))
      (node (ref "R426") (pin "P$1") (pinfunction "P$1_P$1") (pintype "bidirectional"))
    )
    (net (code "84") (name "Net-(R422-PadSENSE-)") (class "Default")
      (node (ref "R422") (pin "SENSE-") (pinfunction "SENSE-_SENSE-") (pintype "bidirectional"))
      (node (ref "R425") (pin "P$1") (pinfunction "P$1_P$1") (pintype "bidirectional"))
    )
    (net (code "85") (name "Net-(R431-PadP$1)") (class "Default")
      (node (ref "R431") (pin "P$1") (pinfunction "P$1_P$1") (pintype "bidirectional"))
      (node (ref "U407") (pin "6") (pinfunction "VO_6") (pintype "bidirectional"))
      (node (ref "U407") (pin "7") (pinfunction "VO_7") (pintype "bidirectional"))
    )
    (net (code "86") (name "Net-(U101-EN)") (class "Default")
      (node (ref "R101") (pin "P$1") (pinfunction "P$1_P$1") (pintype "bidirectional"))
      (node (ref "U101") (pin "1") (pinfunction "EN_1") (pintype "bidirectional"))
    )
    (net (code "87") (name "Net-(U101-OUT)") (class "Default")
      (node (ref "U101") (pin "4") (pinfunction "OUT_4") (pintype "bidirectional"))
      (node (ref "U102") (pin "51") (pinfunction "CLK_51") (pintype "bidirectional"))
    )
    (net (code "88") (name "Net-(U102A-AGPI_A)") (class "Default")
      (node (ref "C114") (pin "P$1") (pinfunction "P$1_P$1") (pintype "bidirectional"))
      (node (ref "R111") (pin "P$1") (pinfunction "P$1_P$1") (pintype "bidirectional"))
      (node (ref "U102") (pin "21") (pinfunction "AGPI_A_21") (pintype "bidirectional"))
    )
    (net (code "89") (name "Net-(U102A-AGPI_B)") (class "Default")
      (node (ref "C115") (pin "P$1") (pinfunction "P$1_P$1") (pintype "bidirectional"))
      (node (ref "R112") (pin "P$2") (pinfunction "P$2_P$2") (pintype "bidirectional"))
      (node (ref "U102") (pin "22") (pinfunction "AGPI_B_22") (pintype "bidirectional"))
    )
    (net (code "90") (name "Net-(U102B-~{RST})") (class "Default")
      (node (ref "R102") (pin "P$2") (pinfunction "P$2_P$2") (pintype "bidirectional"))
      (node (ref "U102") (pin "50") (pinfunction "~{RST}_50") (pintype "bidirectional"))
    )
    (net (code "91") (name "Net-(U102D-ADC_I0_NEG)") (class "Default")
      (node (ref "R117") (pin "P$1") (pinfunction "P$1_P$1") (pintype "bidirectional"))
      (node (ref "R118") (pin "P$2") (pinfunction "P$2_P$2") (pintype "bidirectional"))
      (node (ref "U102") (pin "17") (pinfunction "ADC_I0_NEG_17") (pintype "bidirectional"))
    )
    (net (code "92") (name "Net-(U102D-ADC_I0_POS)") (class "Default")
      (node (ref "C116") (pin "P$1") (pinfunction "P$1_P$1") (pintype "bidirectional"))
      (node (ref "R113") (pin "P$1") (pinfunction "P$1_P$1") (pintype "bidirectional"))
      (node (ref "U102") (pin "16") (pinfunction "ADC_I0_POS_16") (pintype "bidirectional"))
    )
    (net (code "93") (name "Net-(U102D-ADC_I1_NEG)") (class "Default")
      (node (ref "R120") (pin "P$1") (pinfunction "P$1_P$1") (pintype "bidirectional"))
      (node (ref "R121") (pin "P$2") (pinfunction "P$2_P$2") (pintype "bidirectional"))
      (node (ref "U102") (pin "19") (pinfunction "ADC_I1_NEG_19") (pintype "bidirectional"))
    )
    (net (code "94") (name "Net-(U102D-ADC_I1_POS)") (class "Default")
      (node (ref "C117") (pin "P$1") (pinfunction "P$1_P$1") (pintype "bidirectional"))
      (node (ref "R115") (pin "P$1") (pinfunction "P$1_P$1") (pintype "bidirectional"))
      (node (ref "U102") (pin "18") (pinfunction "ADC_I1_POS_18") (pintype "bidirectional"))
    )
    (net (code "95") (name "Net-(U102D-AENC_UX_NEG)") (class "Default")
      (node (ref "R103") (pin "P$1") (pinfunction "P$1_P$1") (pintype "bidirectional"))
      (node (ref "R104") (pin "P$2") (pinfunction "P$2_P$2") (pintype "bidirectional"))
      (node (ref "U102") (pin "26") (pinfunction "AENC_UX_NEG_26") (pintype "bidirectional"))
    )
    (net (code "96") (name "Net-(U102D-AENC_VN_NEG)") (class "Default")
      (node (ref "R106") (pin "P$1") (pinfunction "P$1_P$1") (pintype "bidirectional"))
      (node (ref "R107") (pin "P$2") (pinfunction "P$2_P$2") (pintype "bidirectional"))
      (node (ref "U102") (pin "28") (pinfunction "AENC_VN_NEG_28") (pintype "bidirectional"))
    )
    (net (code "97") (name "Net-(U102D-AENC_WY_NEG)") (class "Default")
      (node (ref "R109") (pin "P$1") (pinfunction "P$1_P$1") (pintype "bidirectional"))
      (node (ref "R110") (pin "P$2") (pinfunction "P$2_P$2") (pintype "bidirectional"))
      (node (ref "U102") (pin "30") (pinfunction "AENC_WY_NEG_30") (pintype "bidirectional"))
    )
    (net (code "98") (name "Net-(U102D-PWM_IDLE_H)") (class "Default")
      (node (ref "R105") (pin "P$2") (pinfunction "P$2_P$2") (pintype "bidirectional"))
      (node (ref "U102") (pin "59") (pinfunction "PWM_IDLE_H_59") (pintype "bidirectional"))
    )
    (net (code "99") (name "Net-(U102D-PWM_IDLE_L)") (class "Default")
      (node (ref "R108") (pin "P$2") (pinfunction "P$2_P$2") (pintype "bidirectional"))
      (node (ref "U102") (pin "60") (pinfunction "PWM_IDLE_L_60") (pintype "bidirectional"))
    )
    (net (code "100") (name "Net-(U201-1)") (class "Default")
      (node (ref "C206") (pin "P$1") (pinfunction "P$1_P$1") (pintype "bidirectional"))
      (node (ref "R201") (pin "P$2") (pinfunction "P$2_P$2") (pintype "bidirectional"))
      (node (ref "R214") (pin "P$2") (pinfunction "P$2_P$2") (pintype "bidirectional"))
      (node (ref "U201") (pin "6") (pinfunction "1_6") (pintype "bidirectional"))
      (node (ref "U205") (pin "1") (pinfunction "A_1") (pintype "input"))
    )
    (net (code "101") (name "Net-(U201-2)") (class "Default")
      (node (ref "C218") (pin "P$1") (pinfunction "P$1_P$1") (pintype "bidirectional"))
      (node (ref "R203") (pin "P$2") (pinfunction "P$2_P$2") (pintype "bidirectional"))
      (node (ref "R223") (pin "P$2") (pinfunction "P$2_P$2") (pintype "bidirectional"))
      (node (ref "U201") (pin "1") (pinfunction "2_1") (pintype "bidirectional"))
      (node (ref "U205") (pin "6") (pinfunction "A_6") (pintype "input"))
    )
    (net (code "102") (name "Net-(U202-1)") (class "Default")
      (node (ref "C207") (pin "P$1") (pinfunction "P$1_P$1") (pintype "bidirectional"))
      (node (ref "R204") (pin "P$2") (pinfunction "P$2_P$2") (pintype "bidirectional"))
      (node (ref "R215") (pin "P$2") (pinfunction "P$2_P$2") (pintype "bidirectional"))
      (node (ref "U202") (pin "6") (pinfunction "1_6") (pintype "bidirectional"))
      (node (ref "U206") (pin "1") (pinfunction "A_1") (pintype "input"))
    )
    (net (code "103") (name "Net-(U202-2)") (class "Default")
      (node (ref "C219") (pin "P$1") (pinfunction "P$1_P$1") (pintype "bidirectional"))
      (node (ref "R206") (pin "P$2") (pinfunction "P$2_P$2") (pintype "bidirectional"))
      (node (ref "R224") (pin "P$2") (pinfunction "P$2_P$2") (pintype "bidirectional"))
      (node (ref "U202") (pin "1") (pinfunction "2_1") (pintype "bidirectional"))
      (node (ref "U206") (pin "6") (pinfunction "A_6") (pintype "input"))
    )
    (net (code "104") (name "Net-(U203-1)") (class "Default")
      (node (ref "C208") (pin "P$1") (pinfunction "P$1_P$1") (pintype "bidirectional"))
      (node (ref "R207") (pin "P$2") (pinfunction "P$2_P$2") (pintype "bidirectional"))
      (node (ref "R216") (pin "P$2") (pinfunction "P$2_P$2") (pintype "bidirectional"))
      (node (ref "U203") (pin "6") (pinfunction "1_6") (pintype "bidirectional"))
      (node (ref "U207") (pin "1") (pinfunction "A_1") (pintype "input"))
    )
    (net (code "105") (name "Net-(U203-2)") (class "Default")
      (node (ref "C220") (pin "P$1") (pinfunction "P$1_P$1") (pintype "bidirectional"))
      (node (ref "R209") (pin "P$2") (pinfunction "P$2_P$2") (pintype "bidirectional"))
      (node (ref "R225") (pin "P$2") (pinfunction "P$2_P$2") (pintype "bidirectional"))
      (node (ref "U203") (pin "1") (pinfunction "2_1") (pintype "bidirectional"))
      (node (ref "U207") (pin "6") (pinfunction "A_6") (pintype "input"))
    )
    (net (code "106") (name "Net-(U204-1)") (class "Default")
      (node (ref "C209") (pin "P$1") (pinfunction "P$1_P$1") (pintype "bidirectional"))
      (node (ref "R210") (pin "P$2") (pinfunction "P$2_P$2") (pintype "bidirectional"))
      (node (ref "R217") (pin "P$2") (pinfunction "P$2_P$2") (pintype "bidirectional"))
      (node (ref "U204") (pin "6") (pinfunction "1_6") (pintype "bidirectional"))
      (node (ref "U208") (pin "1") (pinfunction "A_1") (pintype "input"))
    )
    (net (code "107") (name "Net-(U204-2)") (class "Default")
      (node (ref "C221") (pin "P$1") (pinfunction "P$1_P$1") (pintype "bidirectional"))
      (node (ref "R212") (pin "P$2") (pinfunction "P$2_P$2") (pintype "bidirectional"))
      (node (ref "R226") (pin "P$2") (pinfunction "P$2_P$2") (pintype "bidirectional"))
      (node (ref "U204") (pin "1") (pinfunction "2_1") (pintype "bidirectional"))
      (node (ref "U208") (pin "6") (pinfunction "A_6") (pintype "input"))
    )
    (net (code "108") (name "Net-(U205B-A)") (class "Default")
      (node (ref "C210") (pin "P$1") (pinfunction "P$1_P$1") (pintype "bidirectional"))
      (node (ref "R202") (pin "P$2") (pinfunction "P$2_P$2") (pintype "bidirectional"))
      (node (ref "R219") (pin "P$2") (pinfunction "P$2_P$2") (pintype "bidirectional"))
      (node (ref "U201") (pin "4") (pinfunction "4_4") (pintype "bidirectional"))
      (node (ref "U205") (pin "3") (pinfunction "A_3") (pintype "input"))
    )
    (net (code "109") (name "Net-(U206B-A)") (class "Default")
      (node (ref "C211") (pin "P$1") (pinfunction "P$1_P$1") (pintype "bidirectional"))
      (node (ref "R205") (pin "P$2") (pinfunction "P$2_P$2") (pintype "bidirectional"))
      (node (ref "R220") (pin "P$2") (pinfunction "P$2_P$2") (pintype "bidirectional"))
      (node (ref "U202") (pin "4") (pinfunction "4_4") (pintype "bidirectional"))
      (node (ref "U206") (pin "3") (pinfunction "A_3") (pintype "input"))
    )
    (net (code "110") (name "Net-(U207B-A)") (class "Default")
      (node (ref "C212") (pin "P$1") (pinfunction "P$1_P$1") (pintype "bidirectional"))
      (node (ref "R208") (pin "P$2") (pinfunction "P$2_P$2") (pintype "bidirectional"))
      (node (ref "R221") (pin "P$2") (pinfunction "P$2_P$2") (pintype "bidirectional"))
      (node (ref "U203") (pin "4") (pinfunction "4_4") (pintype "bidirectional"))
      (node (ref "U207") (pin "3") (pinfunction "A_3") (pintype "input"))
    )
    (net (code "111") (name "Net-(U208B-A)") (class "Default")
      (node (ref "C213") (pin "P$1") (pinfunction "P$1_P$1") (pintype "bidirectional"))
      (node (ref "R211") (pin "P$2") (pinfunction "P$2_P$2") (pintype "bidirectional"))
      (node (ref "R222") (pin "P$2") (pinfunction "P$2_P$2") (pintype "bidirectional"))
      (node (ref "U204") (pin "4") (pinfunction "4_4") (pintype "bidirectional"))
      (node (ref "U208") (pin "3") (pinfunction "A_3") (pintype "input"))
    )
    (net (code "112") (name "Net-(U301-FB)") (class "Default")
      (node (ref "R303") (pin "P$1") (pinfunction "P$1_P$1") (pintype "bidirectional"))
      (node (ref "R304") (pin "P$2") (pinfunction "P$2_P$2") (pintype "bidirectional"))
      (node (ref "U301") (pin "1") (pinfunction "FB_1") (pintype "bidirectional"))
    )
    (net (code "113") (name "Net-(U301-ISET)") (class "Default")
      (node (ref "R301") (pin "P$1") (pinfunction "P$1_P$1") (pintype "bidirectional"))
      (node (ref "R302") (pin "P$2") (pinfunction "P$2_P$2") (pintype "bidirectional"))
      (node (ref "U301") (pin "3") (pinfunction "ISET_3") (pintype "bidirectional"))
    )
    (net (code "114") (name "Net-(U401-VDDA)") (class "Default")
      (node (ref "C417") (pin "P$1") (pinfunction "P$1_P$1") (pintype "bidirectional"))
      (node (ref "D401") (pin "C") (pinfunction "C_C") (pintype "passive"))
      (node (ref "U401") (pin "16") (pinfunction "VDDA_16") (pintype "bidirectional"))
    )
    (net (code "115") (name "Net-(U401-VOA)") (class "Default")
      (node (ref "R413") (pin "P$1") (pinfunction "P$1_P$1") (pintype "bidirectional"))
      (node (ref "U401") (pin "15") (pinfunction "VOA_15") (pintype "bidirectional"))
    )
    (net (code "116") (name "Net-(U401-VOB)") (class "Default")
      (node (ref "R417") (pin "P$1") (pinfunction "P$1_P$1") (pintype "bidirectional"))
      (node (ref "U401") (pin "10") (pinfunction "VOB_10") (pintype "bidirectional"))
    )
    (net (code "117") (name "Net-(U402-VDDA)") (class "Default")
      (node (ref "C418") (pin "P$1") (pinfunction "P$1_P$1") (pintype "bidirectional"))
      (node (ref "D402") (pin "C") (pinfunction "C_C") (pintype "passive"))
      (node (ref "U402") (pin "16") (pinfunction "VDDA_16") (pintype "bidirectional"))
    )
    (net (code "118") (name "Net-(U402-VOA)") (class "Default")
      (node (ref "R414") (pin "P$1") (pinfunction "P$1_P$1") (pintype "bidirectional"))
      (node (ref "U402") (pin "15") (pinfunction "VOA_15") (pintype "bidirectional"))
    )
    (net (code "119") (name "Net-(U402-VOB)") (class "Default")
      (node (ref "R418") (pin "P$1") (pinfunction "P$1_P$1") (pintype "bidirectional"))
      (node (ref "U402") (pin "10") (pinfunction "VOB_10") (pintype "bidirectional"))
    )
    (net (code "120") (name "Net-(U403-VDDA)") (class "Default")
      (node (ref "C419") (pin "P$1") (pinfunction "P$1_P$1") (pintype "bidirectional"))
      (node (ref "D403") (pin "C") (pinfunction "C_C") (pintype "passive"))
      (node (ref "U403") (pin "16") (pinfunction "VDDA_16") (pintype "bidirectional"))
    )
    (net (code "121") (name "Net-(U403-VOA)") (class "Default")
      (node (ref "R415") (pin "P$1") (pinfunction "P$1_P$1") (pintype "bidirectional"))
      (node (ref "U403") (pin "15") (pinfunction "VOA_15") (pintype "bidirectional"))
    )
    (net (code "122") (name "Net-(U403-VOB)") (class "Default")
      (node (ref "R419") (pin "P$1") (pinfunction "P$1_P$1") (pintype "bidirectional"))
      (node (ref "U403") (pin "10") (pinfunction "VOB_10") (pintype "bidirectional"))
    )
    (net (code "123") (name "Net-(U404-VDDA)") (class "Default")
      (node (ref "C420") (pin "P$1") (pinfunction "P$1_P$1") (pintype "bidirectional"))
      (node (ref "D404") (pin "C") (pinfunction "C_C") (pintype "passive"))
      (node (ref "U404") (pin "16") (pinfunction "VDDA_16") (pintype "bidirectional"))
    )
    (net (code "124") (name "Net-(U404-VOA)") (class "Default")
      (node (ref "R416") (pin "P$1") (pinfunction "P$1_P$1") (pintype "bidirectional"))
      (node (ref "U404") (pin "15") (pinfunction "VOA_15") (pintype "bidirectional"))
    )
    (net (code "125") (name "Net-(U404-VOB)") (class "Default")
      (node (ref "R420") (pin "P$1") (pinfunction "P$1_P$1") (pintype "bidirectional"))
      (node (ref "U404") (pin "10") (pinfunction "VOB_10") (pintype "bidirectional"))
    )
    (net (code "126") (name "Net-(U405E-IN+)") (class "Default")
      (node (ref "C427") (pin "P$2") (pinfunction "P$2_P$2") (pintype "bidirectional"))
      (node (ref "C428") (pin "P$1") (pinfunction "P$1_P$1") (pintype "bidirectional"))
      (node (ref "R424") (pin "P$2") (pinfunction "P$2_P$2") (pintype "bidirectional"))
      (node (ref "U405") (pin "8") (pinfunction "IN+_8") (pintype "bidirectional"))
    )
    (net (code "127") (name "Net-(U405E-IN-)") (class "Default")
      (node (ref "C426") (pin "P$2") (pinfunction "P$2_P$2") (pintype "bidirectional"))
      (node (ref "C427") (pin "P$1") (pinfunction "P$1_P$1") (pintype "bidirectional"))
      (node (ref "R423") (pin "P$2") (pinfunction "P$2_P$2") (pintype "bidirectional"))
      (node (ref "U405") (pin "1") (pinfunction "IN-_1") (pintype "bidirectional"))
    )
    (net (code "128") (name "Net-(U406E-IN+)") (class "Default")
      (node (ref "C430") (pin "P$2") (pinfunction "P$2_P$2") (pintype "bidirectional"))
      (node (ref "C431") (pin "P$1") (pinfunction "P$1_P$1") (pintype "bidirectional"))
      (node (ref "R426") (pin "P$2") (pinfunction "P$2_P$2") (pintype "bidirectional"))
      (node (ref "U406") (pin "8") (pinfunction "IN+_8") (pintype "bidirectional"))
    )
    (net (code "129") (name "Net-(U406E-IN-)") (class "Default")
      (node (ref "C429") (pin "P$2") (pinfunction "P$2_P$2") (pintype "bidirectional"))
      (node (ref "C430") (pin "P$1") (pinfunction "P$1_P$1") (pintype "bidirectional"))
      (node (ref "R425") (pin "P$2") (pinfunction "P$2_P$2") (pintype "bidirectional"))
      (node (ref "U406") (pin "1") (pinfunction "IN-_1") (pintype "bidirectional"))
    )
    (net (code "130") (name "Net-(U407-AN)") (class "Default")
      (node (ref "R429") (pin "P$1") (pinfunction "P$1_P$1") (pintype "bidirectional"))
      (node (ref "U407") (pin "2") (pinfunction "AN_2") (pintype "bidirectional"))
    )
    (net (code "131") (name "Net-(U501-(CTS)GPIO4-~{CS4}-EVTCNTR)") (class "Default")
      (node (ref "JP507") (pin "1") (pinfunction "1_1") (pintype "passive"))
      (node (ref "U501") (pin "18") (pinfunction "(CTS)GPIO4-~{CS4}-EVTCNTR_18") (pintype "bidirectional"))
    )
    (net (code "132") (name "Net-(U501-(DCD)MISO)") (class "Default")
      (node (ref "JP501") (pin "1") (pinfunction "1_1") (pintype "passive"))
      (node (ref "U501") (pin "24") (pinfunction "(DCD)MISO_24") (pintype "bidirectional"))
    )
    (net (code "133") (name "Net-(U501-(DSR)GPIO0-~{CS0})") (class "Default")
      (node (ref "JP504") (pin "1") (pinfunction "1_1") (pintype "passive"))
      (node (ref "U501") (pin "22") (pinfunction "(DSR)GPIO0-~{CS0}_22") (pintype "bidirectional"))
    )
    (net (code "134") (name "Net-(U501-(DTR)MOSI)") (class "Default")
      (node (ref "JP502") (pin "1") (pinfunction "1_1") (pintype "passive"))
      (node (ref "U501") (pin "23") (pinfunction "(DTR)MOSI_23") (pintype "bidirectional"))
    )
    (net (code "135") (name "Net-(U501-(RI{slash}CLK)SCK)") (class "Default")
      (node (ref "JP503") (pin "1") (pinfunction "1_1") (pintype "passive"))
      (node (ref "U501") (pin "1") (pinfunction "(RI/CLK)SCK_1") (pintype "bidirectional"))
    )
    (net (code "136") (name "Net-(U501-(RXD)GPIO2-~{CS2})") (class "Default")
      (node (ref "JP506") (pin "1") (pinfunction "1_1") (pintype "passive"))
      (node (ref "U501") (pin "20") (pinfunction "(RXD)GPIO2-~{CS2}_20") (pintype "bidirectional"))
    )
    (net (code "137") (name "Net-(U501-(TXD)GPIO1-~{CS1})") (class "Default")
      (node (ref "JP505") (pin "1") (pinfunction "1_1") (pintype "passive"))
      (node (ref "U501") (pin "21") (pinfunction "(TXD)GPIO1-~{CS1}_21") (pintype "bidirectional"))
    )
    (net (code "138") (name "Net-(U501-VPP)") (class "Default")
      (node (ref "C503") (pin "P$1") (pinfunction "P$1_P$1") (pintype "bidirectional"))
      (node (ref "U501") (pin "16") (pinfunction "VPP_16") (pintype "bidirectional"))
    )
    (net (code "139") (name "Net-(U501-~{RST})") (class "Default")
      (node (ref "R501") (pin "P$2") (pinfunction "P$2_P$2") (pintype "bidirectional"))
      (node (ref "U501") (pin "9") (pinfunction "~{RST}_9") (pintype "bidirectional"))
    )
    (net (code "140") (name "PWM_IN") (class "Default")
      (node (ref "D504") (pin "P$3") (pinfunction "3_P$3") (pintype "bidirectional"))
      (node (ref "R504") (pin "P$2") (pinfunction "P$2_P$2") (pintype "bidirectional"))
      (node (ref "R505") (pin "P$2") (pinfunction "P$2_P$2") (pintype "bidirectional"))
      (node (ref "U102") (pin "58") (pinfunction "PWM_IN_58") (pintype "bidirectional"))
    )
    (net (code "141") (name "PWM_UX1_H") (class "Default")
      (node (ref "R405") (pin "P$2") (pinfunction "P$2_P$2") (pintype "bidirectional"))
      (node (ref "U102") (pin "39") (pinfunction "PWM_UX1_H_39") (pintype "bidirectional"))
      (node (ref "U401") (pin "1") (pinfunction "VIA_1") (pintype "bidirectional"))
    )
    (net (code "142") (name "PWM_UX1_L") (class "Default")
      (node (ref "R401") (pin "P$2") (pinfunction "P$2_P$2") (pintype "bidirectional"))
      (node (ref "U102") (pin "40") (pinfunction "PWM_UX1_L_40") (pintype "bidirectional"))
      (node (ref "U401") (pin "2") (pinfunction "VIB_2") (pintype "bidirectional"))
    )
    (net (code "143") (name "PWM_VX2_H") (class "Default")
      (node (ref "R406") (pin "P$2") (pinfunction "P$2_P$2") (pintype "bidirectional"))
      (node (ref "U102") (pin "41") (pinfunction "PWM_VX2_H_41") (pintype "bidirectional"))
      (node (ref "U402") (pin "1") (pinfunction "VIA_1") (pintype "bidirectional"))
    )
    (net (code "144") (name "PWM_VX2_L") (class "Default")
      (node (ref "R402") (pin "P$2") (pinfunction "P$2_P$2") (pintype "bidirectional"))
      (node (ref "U102") (pin "42") (pinfunction "PWM_VX2_L_42") (pintype "bidirectional"))
      (node (ref "U402") (pin "2") (pinfunction "VIB_2") (pintype "bidirectional"))
    )
    (net (code "145") (name "PWM_WY1_H") (class "Default")
      (node (ref "R407") (pin "P$2") (pinfunction "P$2_P$2") (pintype "bidirectional"))
      (node (ref "U102") (pin "46") (pinfunction "PWM_WY1_H_46") (pintype "bidirectional"))
      (node (ref "U403") (pin "1") (pinfunction "VIA_1") (pintype "bidirectional"))
    )
    (net (code "146") (name "PWM_WY1_L") (class "Default")
      (node (ref "R403") (pin "P$2") (pinfunction "P$2_P$2") (pintype "bidirectional"))
      (node (ref "U102") (pin "47") (pinfunction "PWM_WY1_L_47") (pintype "bidirectional"))
      (node (ref "U403") (pin "2") (pinfunction "VIB_2") (pintype "bidirectional"))
    )
    (net (code "147") (name "PWM_Y2_H") (class "Default")
      (node (ref "R408") (pin "P$2") (pinfunction "P$2_P$2") (pintype "bidirectional"))
      (node (ref "U102") (pin "48") (pinfunction "PWM_Y2_H_48") (pintype "bidirectional"))
      (node (ref "U404") (pin "1") (pinfunction "VIA_1") (pintype "bidirectional"))
    )
    (net (code "148") (name "PWM_Y2_L") (class "Default")
      (node (ref "R404") (pin "P$2") (pinfunction "P$2_P$2") (pintype "bidirectional"))
      (node (ref "U102") (pin "49") (pinfunction "PWM_Y2_L_49") (pintype "bidirectional"))
      (node (ref "U404") (pin "2") (pinfunction "VIB_2") (pintype "bidirectional"))
    )
    (net (code "149") (name "REF_H") (class "Default")
      (node (ref "U102") (pin "68") (pinfunction "REF_H_68") (pintype "bidirectional"))
      (node (ref "U208") (pin "5") (pinfunction "Y_5") (pintype "output"))
    )
    (net (code "150") (name "REF_L") (class "Default")
      (node (ref "U102") (pin "67") (pinfunction "REF_L_67") (pintype "bidirectional"))
      (node (ref "U208") (pin "2") (pinfunction "Y_2") (pintype "output"))
    )
    (net (code "151") (name "REF_R") (class "Default")
      (node (ref "U102") (pin "69") (pinfunction "REF_R_69") (pintype "bidirectional"))
      (node (ref "U208") (pin "7") (pinfunction "Y_7") (pintype "output"))
    )
    (net (code "152") (name "SCK") (class "Default")
      (node (ref "J501") (pin "2") (pinfunction "S_2") (pintype "passive"))
      (node (ref "JP503") (pin "2") (pinfunction "2_2") (pintype "passive"))
      (node (ref "U102") (pin "7") (pinfunction "SPI_SCK_7") (pintype "bidirectional"))
    )
    (net (code "153") (name "STEP") (class "Default")
      (node (ref "D506") (pin "P$3") (pinfunction "3_P$3") (pintype "bidirectional"))
      (node (ref "R509") (pin "P$2") (pinfunction "P$2_P$2") (pintype "bidirectional"))
      (node (ref "R510") (pin "P$2") (pinfunction "P$2_P$2") (pintype "bidirectional"))
      (node (ref "U102") (pin "57") (pinfunction "STP_57") (pintype "bidirectional"))
    )
    (net (code "154") (name "UX1") (class "Default")
      (node (ref "C417") (pin "P$2") (pinfunction "P$2_P$2") (pintype "bidirectional"))
      (node (ref "Q401") (pin "S1") (pinfunction "S1_S1") (pintype "bidirectional"))
      (node (ref "Q401") (pin "S2") (pinfunction "S1_S2") (pintype "bidirectional"))
      (node (ref "Q401") (pin "S3") (pinfunction "S1_S3") (pintype "bidirectional"))
      (node (ref "Q401") (pin "S4") (pinfunction "S1_S4") (pintype "bidirectional"))
      (node (ref "Q401") (pin "S5") (pinfunction "S1_S5") (pintype "bidirectional"))
      (node (ref "Q405") (pin "D1") (pinfunction "D1_D1") (pintype "bidirectional"))
      (node (ref "Q405") (pin "D2") (pinfunction "D1_D2") (pintype "bidirectional"))
      (node (ref "Q405") (pin "D3") (pinfunction "D1_D3") (pintype "bidirectional"))
      (node (ref "Q405") (pin "D4") (pinfunction "D1_D4") (pintype "bidirectional"))
      (node (ref "R421") (pin "1") (pinfunction "P$1_1") (pintype "bidirectional"))
      (node (ref "R421") (pin "2") (pinfunction "P$1_2") (pintype "bidirectional"))
      (node (ref "U401") (pin "14") (pinfunction "GNDA_14") (pintype "bidirectional"))
    )
    (net (code "155") (name "VBUS") (class "Default")
      (node (ref "R506") (pin "P$2") (pinfunction "P$2_P$2") (pintype "bidirectional"))
      (node (ref "R507") (pin "P$1") (pinfunction "P$1_P$1") (pintype "bidirectional"))
      (node (ref "U501") (pin "8") (pinfunction "VBUS_8") (pintype "bidirectional"))
    )
    (net (code "156") (name "VX2") (class "Default")
      (node (ref "C418") (pin "P$2") (pinfunction "P$2_P$2") (pintype "bidirectional"))
      (node (ref "J401") (pin "2") (pinfunction "S_2") (pintype "passive"))
      (node (ref "P401") (pin "H1") (pinfunction "S_H1") (pintype "passive"))
      (node (ref "P401") (pin "H10") (pinfunction "S_H10") (pintype "passive"))
      (node (ref "P401") (pin "H11") (pinfunction "S_H11") (pintype "passive"))
      (node (ref "P401") (pin "H12") (pinfunction "S_H12") (pintype "passive"))
      (node (ref "P401") (pin "H2") (pinfunction "S_H2") (pintype "passive"))
      (node (ref "P401") (pin "H3") (pinfunction "S_H3") (pintype "passive"))
      (node (ref "P401") (pin "H4") (pinfunction "S_H4") (pintype "passive"))
      (node (ref "P401") (pin "H5") (pinfunction "S_H5") (pintype "passive"))
      (node (ref "P401") (pin "H6") (pinfunction "S_H6") (pintype "passive"))
      (node (ref "P401") (pin "H7") (pinfunction "S_H7") (pintype "passive"))
      (node (ref "P401") (pin "H8") (pinfunction "S_H8") (pintype "passive"))
      (node (ref "P401") (pin "H9") (pinfunction "S_H9") (pintype "passive"))
      (node (ref "P401") (pin "PAD") (pinfunction "S_PAD") (pintype "passive"))
      (node (ref "Q402") (pin "S1") (pinfunction "S1_S1") (pintype "bidirectional"))
      (node (ref "Q402") (pin "S2") (pinfunction "S1_S2") (pintype "bidirectional"))
      (node (ref "Q402") (pin "S3") (pinfunction "S1_S3") (pintype "bidirectional"))
      (node (ref "Q402") (pin "S4") (pinfunction "S1_S4") (pintype "bidirectional"))
      (node (ref "Q402") (pin "S5") (pinfunction "S1_S5") (pintype "bidirectional"))
      (node (ref "Q406") (pin "D1") (pinfunction "D1_D1") (pintype "bidirectional"))
      (node (ref "Q406") (pin "D2") (pinfunction "D1_D2") (pintype "bidirectional"))
      (node (ref "Q406") (pin "D3") (pinfunction "D1_D3") (pintype "bidirectional"))
      (node (ref "Q406") (pin "D4") (pinfunction "D1_D4") (pintype "bidirectional"))
      (node (ref "U402") (pin "14") (pinfunction "GNDA_14") (pintype "bidirectional"))
    )
    (net (code "157") (name "WY1") (class "Default")
      (node (ref "C419") (pin "P$2") (pinfunction "P$2_P$2") (pintype "bidirectional"))
      (node (ref "Q403") (pin "S1") (pinfunction "S1_S1") (pintype "bidirectional"))
      (node (ref "Q403") (pin "S2") (pinfunction "S1_S2") (pintype "bidirectional"))
      (node (ref "Q403") (pin "S3") (pinfunction "S1_S3") (pintype "bidirectional"))
      (node (ref "Q403") (pin "S4") (pinfunction "S1_S4") (pintype "bidirectional"))
      (node (ref "Q403") (pin "S5") (pinfunction "S1_S5") (pintype "bidirectional"))
      (node (ref "Q407") (pin "D1") (pinfunction "D1_D1") (pintype "bidirectional"))
      (node (ref "Q407") (pin "D2") (pinfunction "D1_D2") (pintype "bidirectional"))
      (node (ref "Q407") (pin "D3") (pinfunction "D1_D3") (pintype "bidirectional"))
      (node (ref "Q407") (pin "D4") (pinfunction "D1_D4") (pintype "bidirectional"))
      (node (ref "R422") (pin "1") (pinfunction "P$1_1") (pintype "bidirectional"))
      (node (ref "R422") (pin "2") (pinfunction "P$1_2") (pintype "bidirectional"))
      (node (ref "U403") (pin "14") (pinfunction "GNDA_14") (pintype "bidirectional"))
    )
    (net (code "158") (name "Y2") (class "Default")
      (node (ref "C420") (pin "P$2") (pinfunction "P$2_P$2") (pintype "bidirectional"))
      (node (ref "J401") (pin "4") (pinfunction "S_4") (pintype "passive"))
      (node (ref "P402") (pin "H1") (pinfunction "S_H1") (pintype "passive"))
      (node (ref "P402") (pin "H10") (pinfunction "S_H10") (pintype "passive"))
      (node (ref "P402") (pin "H11") (pinfunction "S_H11") (pintype "passive"))
      (node (ref "P402") (pin "H12") (pinfunction "S_H12") (pintype "passive"))
      (node (ref "P402") (pin "H2") (pinfunction "S_H2") (pintype "passive"))
      (node (ref "P402") (pin "H3") (pinfunction "S_H3") (pintype "passive"))
      (node (ref "P402") (pin "H4") (pinfunction "S_H4") (pintype "passive"))
      (node (ref "P402") (pin "H5") (pinfunction "S_H5") (pintype "passive"))
      (node (ref "P402") (pin "H6") (pinfunction "S_H6") (pintype "passive"))
      (node (ref "P402") (pin "H7") (pinfunction "S_H7") (pintype "passive"))
      (node (ref "P402") (pin "H8") (pinfunction "S_H8") (pintype "passive"))
      (node (ref "P402") (pin "H9") (pinfunction "S_H9") (pintype "passive"))
      (node (ref "P402") (pin "PAD") (pinfunction "S_PAD") (pintype "passive"))
      (node (ref "Q404") (pin "S1") (pinfunction "S1_S1") (pintype "bidirectional"))
      (node (ref "Q404") (pin "S2") (pinfunction "S1_S2") (pintype "bidirectional"))
      (node (ref "Q404") (pin "S3") (pinfunction "S1_S3") (pintype "bidirectional"))
      (node (ref "Q404") (pin "S4") (pinfunction "S1_S4") (pintype "bidirectional"))
      (node (ref "Q404") (pin "S5") (pinfunction "S1_S5") (pintype "bidirectional"))
      (node (ref "Q408") (pin "D1") (pinfunction "D1_D1") (pintype "bidirectional"))
      (node (ref "Q408") (pin "D2") (pinfunction "D1_D2") (pintype "bidirectional"))
      (node (ref "Q408") (pin "D3") (pinfunction "D1_D3") (pintype "bidirectional"))
      (node (ref "Q408") (pin "D4") (pinfunction "D1_D4") (pintype "bidirectional"))
      (node (ref "U404") (pin "14") (pinfunction "GNDA_14") (pintype "bidirectional"))
    )
    (net (code "159") (name "unconnected-(J505C-S-Pad2)") (class "Default")
      (node (ref "J505") (pin "2") (pinfunction "S_2") (pintype "passive"))
    )
    (net (code "160") (name "unconnected-(U102A-ENI-Pad55)") (class "Default")
      (node (ref "U102") (pin "55") (pinfunction "ENI_55") (pintype "bidirectional"))
    )
    (net (code "161") (name "unconnected-(U102A-GPIO0-Pad70)") (class "Default")
      (node (ref "U102") (pin "70") (pinfunction "GPIO0_70") (pintype "bidirectional"))
    )
    (net (code "162") (name "unconnected-(U102A-GPIO1-Pad71)") (class "Default")
      (node (ref "U102") (pin "71") (pinfunction "GPIO1_71") (pintype "bidirectional"))
    )
    (net (code "163") (name "unconnected-(U102A-GPIO2-Pad74)") (class "Default")
      (node (ref "U102") (pin "74") (pinfunction "GPIO2_74") (pintype "bidirectional"))
    )
    (net (code "164") (name "unconnected-(U201-Pad3)") (class "Default")
      (node (ref "U201") (pin "3") (pinfunction "3_3") (pintype "bidirectional"))
    )
    (net (code "165") (name "unconnected-(U202-Pad3)") (class "Default")
      (node (ref "U202") (pin "3") (pinfunction "3_3") (pintype "bidirectional"))
    )
    (net (code "166") (name "unconnected-(U203-Pad3)") (class "Default")
      (node (ref "U203") (pin "3") (pinfunction "3_3") (pintype "bidirectional"))
    )
    (net (code "167") (name "unconnected-(U204-Pad3)") (class "Default")
      (node (ref "U204") (pin "3") (pinfunction "3_3") (pintype "bidirectional"))
    )
    (net (code "168") (name "unconnected-(U501-(GPIO2-RS485)GPIO9-~{CS9}-SUSPEND-Pad12)") (class "Default")
      (node (ref "U501") (pin "12") (pinfunction "(GPIO2-RS485)GPIO9-~{CS9}-SUSPEND_12") (pintype "bidirectional"))
    )
    (net (code "169") (name "unconnected-(U501-(GPIO3-WKUP)GPIO10-~{CS10}-~{SUSPEND}-Pad11)") (class "Default")
      (node (ref "U501") (pin "11") (pinfunction "(GPIO3-WKUP)GPIO10-~{CS10}-~{SUSPEND}_11") (pintype "bidirectional"))
    )
    (net (code "170") (name "unconnected-(U501-(RTS)GPIO3-~{CS3}-RTR-Pad19)") (class "Default")
      (node (ref "U501") (pin "19") (pinfunction "(RTS)GPIO3-~{CS3}-RTR_19") (pintype "bidirectional"))
    )
    (net (code "171") (name "unconnected-(U501-(SUSPEND)GPIO5-~{CS5}-CLKOUT-Pad17)") (class "Default")
      (node (ref "U501") (pin "17") (pinfunction "(SUSPEND)GPIO5-~{CS5}-CLKOUT_17") (pintype "bidirectional"))
    )
    (net (code "172") (name "unconnected-(U501-(~{SUSPEND})GPIO6-~{CS6}-Pad15)") (class "Default")
      (node (ref "U501") (pin "15") (pinfunction "(~{SUSPEND})GPIO6-~{CS6}_15") (pintype "bidirectional"))
    )
    (net (code "173") (name "~{CS}") (class "Default")
      (node (ref "J501") (pin "1") (pinfunction "S_1") (pintype "passive"))
      (node (ref "JP504") (pin "2") (pinfunction "2_2") (pintype "passive"))
      (node (ref "U102") (pin "6") (pinfunction "SPI_NSCS_6") (pintype "bidirectional"))
    )
  )
)
